# PCB_Ver_1_0.net
KiCad netlist of a schematic drawn in Altium Designer
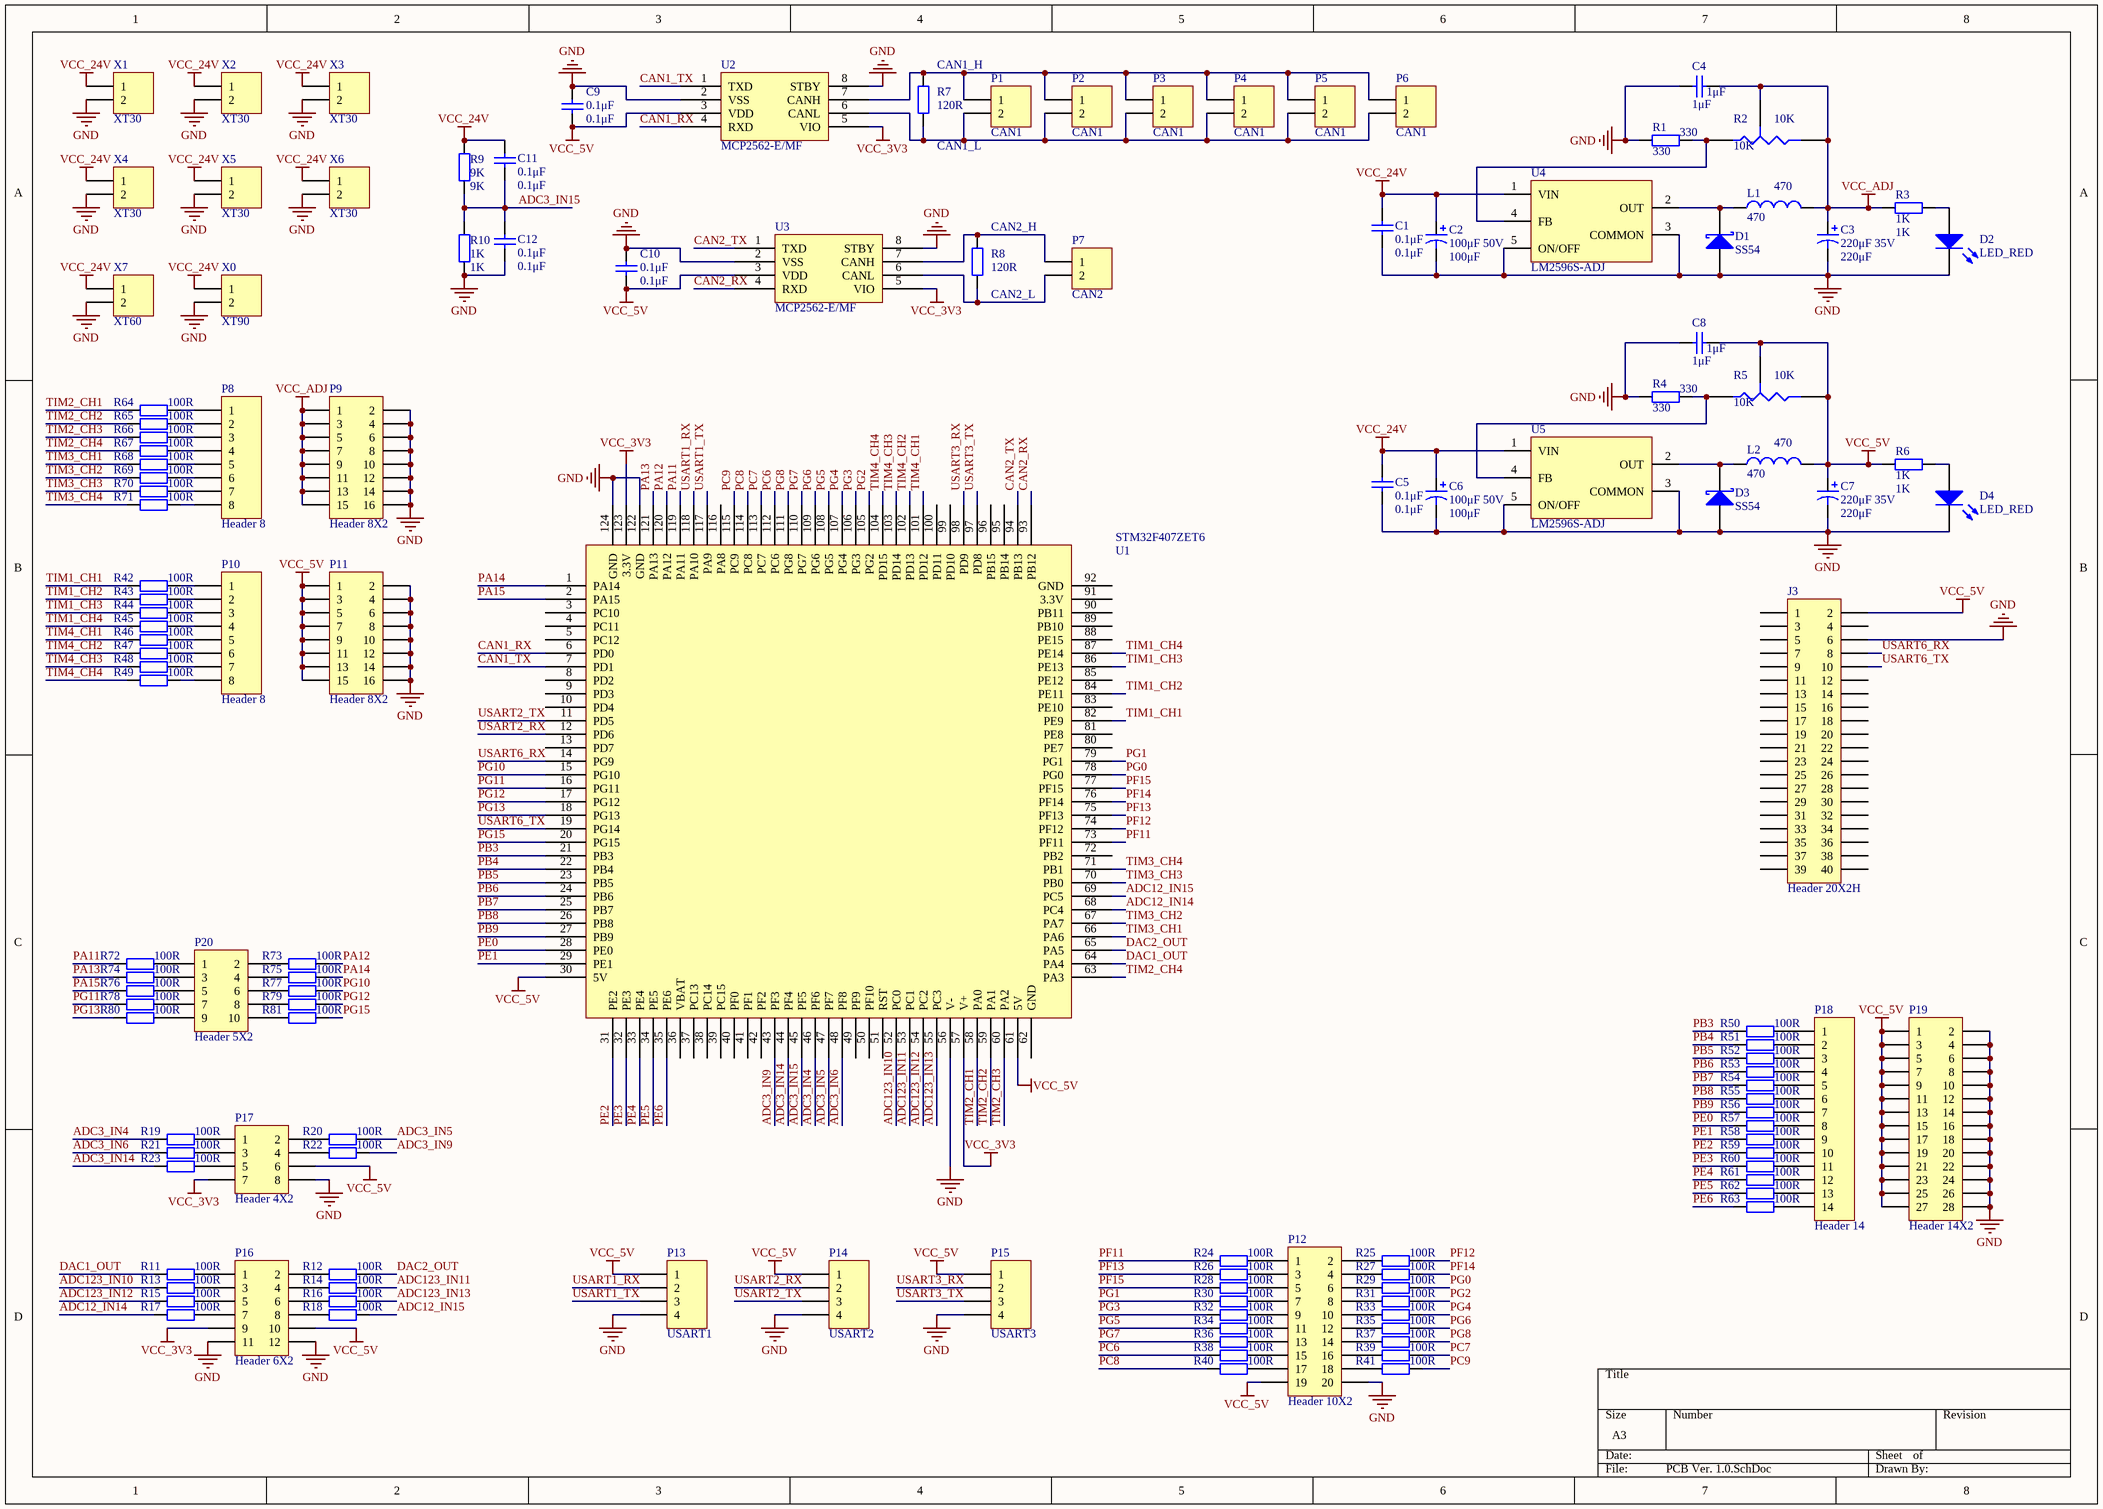
[diagram p0: PCB Ver. 1.0.SchDoc]

(export (version "E")
  (design (tool "Eeschema 10.0.6"))
  (components
    (comp (ref "C1")
      (value "0.1μF")
      (footprint "6-0805_N")
      (description "Capacitor")
      (fields (field (name "ALTIUM_VALUE") "0.1μF") (field (name "PUBLISHER") "Altium Limited"))
      (libsource (lib "Miscellaneous Devices") (part "Cap"))
    )
    (comp (ref "C2")
      (value "100μF 50V")
      (footprint "8*12直插铝电解")
      (description "Polarized Capacitor (Radial)")
      (fields (field (name "ALTIUM_VALUE") "100μF") (field (name "PUBLISHER") "Altium Limited"))
      (libsource (lib "Miscellaneous Devices") (part "Cap Pol1"))
    )
    (comp (ref "C3")
      (value "220μF 35V")
      (footprint "8*12直插铝电解")
      (description "Polarized Capacitor (Radial)")
      (fields (field (name "ALTIUM_VALUE") "220μF") (field (name "PUBLISHER") "Altium Limited"))
      (libsource (lib "Miscellaneous Devices") (part "Cap Pol1"))
    )
    (comp (ref "C4")
      (value "1μF")
      (footprint "6-0805_N")
      (description "Capacitor")
      (fields (field (name "ALTIUM_VALUE") "1μF") (field (name "PUBLISHER") "Altium Limited"))
      (libsource (lib "Miscellaneous Devices") (part "Cap"))
    )
    (comp (ref "C5")
      (value "0.1μF")
      (footprint "6-0805_N")
      (description "Capacitor")
      (fields (field (name "ALTIUM_VALUE") "0.1μF") (field (name "PUBLISHER") "Altium Limited"))
      (libsource (lib "Miscellaneous Devices") (part "Cap"))
    )
    (comp (ref "C6")
      (value "100μF 50V")
      (footprint "8*12直插铝电解")
      (description "Polarized Capacitor (Radial)")
      (fields (field (name "ALTIUM_VALUE") "100μF") (field (name "PUBLISHER") "Altium Limited"))
      (libsource (lib "Miscellaneous Devices") (part "Cap Pol1"))
    )
    (comp (ref "C7")
      (value "220μF 35V")
      (footprint "8*12直插铝电解")
      (description "Polarized Capacitor (Radial)")
      (fields (field (name "ALTIUM_VALUE") "220μF") (field (name "PUBLISHER") "Altium Limited"))
      (libsource (lib "Miscellaneous Devices") (part "Cap Pol1"))
    )
    (comp (ref "C8")
      (value "1μF")
      (footprint "6-0805_N")
      (description "Capacitor")
      (fields (field (name "ALTIUM_VALUE") "1μF") (field (name "PUBLISHER") "Altium Limited"))
      (libsource (lib "Miscellaneous Devices") (part "Cap"))
    )
    (comp (ref "C9")
      (value "0.1μF")
      (footprint "6-0805_N")
      (description "Capacitor")
      (fields (field (name "ALTIUM_VALUE") "0.1μF") (field (name "PUBLISHER") "Altium Limited"))
      (libsource (lib "Miscellaneous Devices") (part "Cap"))
    )
    (comp (ref "C10")
      (value "0.1μF")
      (footprint "6-0805_N")
      (description "Capacitor")
      (fields (field (name "ALTIUM_VALUE") "0.1μF") (field (name "PUBLISHER") "Altium Limited"))
      (libsource (lib "Miscellaneous Devices") (part "Cap"))
    )
    (comp (ref "C11")
      (value "0.1μF")
      (footprint "6-0805_N")
      (description "Capacitor")
      (fields (field (name "ALTIUM_VALUE") "0.1μF") (field (name "PUBLISHER") "Altium Limited"))
      (libsource (lib "Miscellaneous Devices") (part "Cap"))
    )
    (comp (ref "C12")
      (value "0.1μF")
      (footprint "6-0805_N")
      (description "Capacitor")
      (fields (field (name "ALTIUM_VALUE") "0.1μF") (field (name "PUBLISHER") "Altium Limited"))
      (libsource (lib "Miscellaneous Devices") (part "Cap"))
    )
    (comp (ref "D1")
      (value "SS54")
      (footprint "DO-214AA")
      (description "Schottky Rectifier")
      (fields (field (name "PUBLISHER") "Altium Limited"))
      (libsource (lib "Miscellaneous Devices") (part "Diode 11DQ03"))
    )
    (comp (ref "D2")
      (value "LED_RED")
      (footprint "1206_LED")
      (description "Typical BLUE SiC LED")
      (fields (field (name "PUBLISHER") "Altium Limited"))
      (libsource (lib "Miscellaneous Devices") (part "LED3"))
    )
    (comp (ref "D3")
      (value "SS54")
      (footprint "DO-214AA")
      (description "Schottky Rectifier")
      (fields (field (name "PUBLISHER") "Altium Limited"))
      (libsource (lib "Miscellaneous Devices") (part "Diode 11DQ03"))
    )
    (comp (ref "D4")
      (value "LED_RED")
      (footprint "1206_LED")
      (description "Typical BLUE SiC LED")
      (fields (field (name "PUBLISHER") "Altium Limited"))
      (libsource (lib "Miscellaneous Devices") (part "LED3"))
    )
    (comp (ref "J3")
      (value "Header 20X2H")
      (footprint "HDR2X20")
      (description "Header, 20-Pin, Dual row, Right Angle")
      (fields (field (name "PUBLISHER") "Altium Limited"))
      (libsource (lib "Miscellaneous Connectors") (part "Header 20X2H"))
    )
    (comp (ref "L1")
      (value "470")
      (footprint "12*12*7贴片电感")
      (description "Inductor")
      (fields (field (name "ALTIUM_VALUE") "470") (field (name "PUBLISHER") "Altium Limited"))
      (libsource (lib "Miscellaneous Devices") (part "Inductor"))
    )
    (comp (ref "L2")
      (value "470")
      (footprint "12*12*7贴片电感")
      (description "Inductor")
      (fields (field (name "ALTIUM_VALUE") "470") (field (name "PUBLISHER") "Altium Limited"))
      (libsource (lib "Miscellaneous Devices") (part "Inductor"))
    )
    (comp (ref "P1")
      (value "CAN1")
      (footprint "MHDR1X2")
      (description "Header, 2-Pin")
      (fields (field (name "PUBLISHER") "Altium Limited"))
      (libsource (lib "Miscellaneous Connectors") (part "Header 2"))
    )
    (comp (ref "P2")
      (value "CAN1")
      (footprint "MHDR1X2")
      (description "Header, 2-Pin")
      (fields (field (name "PUBLISHER") "Altium Limited"))
      (libsource (lib "Miscellaneous Connectors") (part "Header 2"))
    )
    (comp (ref "P3")
      (value "CAN1")
      (footprint "MHDR1X2")
      (description "Header, 2-Pin")
      (fields (field (name "PUBLISHER") "Altium Limited"))
      (libsource (lib "Miscellaneous Connectors") (part "Header 2"))
    )
    (comp (ref "P4")
      (value "CAN1")
      (footprint "MHDR1X2")
      (description "Header, 2-Pin")
      (fields (field (name "PUBLISHER") "Altium Limited"))
      (libsource (lib "Miscellaneous Connectors") (part "Header 2"))
    )
    (comp (ref "P5")
      (value "CAN1")
      (footprint "MHDR1X2")
      (description "Header, 2-Pin")
      (fields (field (name "PUBLISHER") "Altium Limited"))
      (libsource (lib "Miscellaneous Connectors") (part "Header 2"))
    )
    (comp (ref "P6")
      (value "CAN1")
      (footprint "MHDR1X2")
      (description "Header, 2-Pin")
      (fields (field (name "PUBLISHER") "Altium Limited"))
      (libsource (lib "Miscellaneous Connectors") (part "Header 2"))
    )
    (comp (ref "P7")
      (value "CAN2")
      (footprint "HDR1X2")
      (description "Header, 2-Pin")
      (fields (field (name "PUBLISHER") "Altium Limited"))
      (libsource (lib "Miscellaneous Connectors") (part "Header 2"))
    )
    (comp (ref "P8")
      (value "Header 8")
      (footprint "HDR1X8")
      (description "Header, 8-Pin")
      (fields (field (name "PUBLISHER") "Altium Limited"))
      (libsource (lib "Miscellaneous Connectors") (part "Header 8"))
    )
    (comp (ref "P9")
      (value "Header 8X2")
      (footprint "HDR2X8")
      (description "Header, 8-Pin, Dual row")
      (fields (field (name "PUBLISHER") "Altium Limited"))
      (libsource (lib "Miscellaneous Connectors") (part "Header 8X2"))
    )
    (comp (ref "P10")
      (value "Header 8")
      (footprint "HDR1X8")
      (description "Header, 8-Pin")
      (fields (field (name "PUBLISHER") "Altium Limited"))
      (libsource (lib "Miscellaneous Connectors") (part "Header 8"))
    )
    (comp (ref "P11")
      (value "Header 8X2")
      (footprint "HDR2X8")
      (description "Header, 8-Pin, Dual row")
      (fields (field (name "PUBLISHER") "Altium Limited"))
      (libsource (lib "Miscellaneous Connectors") (part "Header 8X2"))
    )
    (comp (ref "P12")
      (value "Header 10X2")
      (footprint "HDR2X10")
      (description "Header, 10-Pin, Dual row")
      (fields (field (name "PUBLISHER") "Altium Limited"))
      (libsource (lib "Miscellaneous Connectors") (part "Header 10X2"))
    )
    (comp (ref "P13")
      (value "USART1")
      (footprint "HDR1X4")
      (description "Header, 4-Pin")
      (fields (field (name "PUBLISHER") "Altium Limited"))
      (libsource (lib "Miscellaneous Connectors") (part "Header 4"))
    )
    (comp (ref "P14")
      (value "USART2")
      (footprint "HDR1X4")
      (description "Header, 4-Pin")
      (fields (field (name "PUBLISHER") "Altium Limited"))
      (libsource (lib "Miscellaneous Connectors") (part "Header 4"))
    )
    (comp (ref "P15")
      (value "USART3")
      (footprint "HDR1X4")
      (description "Header, 4-Pin")
      (fields (field (name "PUBLISHER") "Altium Limited"))
      (libsource (lib "Miscellaneous Connectors") (part "Header 4"))
    )
    (comp (ref "P16")
      (value "Header 6X2")
      (footprint "HDR2X6")
      (description "Header, 6-Pin, Dual row")
      (fields (field (name "PUBLISHER") "Altium Limited"))
      (libsource (lib "Miscellaneous Connectors") (part "Header 6X2"))
    )
    (comp (ref "P17")
      (value "Header 4X2")
      (footprint "HDR2X4")
      (description "Header, 4-Pin, Dual row")
      (fields (field (name "PUBLISHER") "Altium Limited"))
      (libsource (lib "Miscellaneous Connectors") (part "Header 4X2"))
    )
    (comp (ref "P18")
      (value "Header 14")
      (footprint "HDR1X14")
      (description "Header, 14-Pin")
      (fields (field (name "PUBLISHER") "Altium Limited"))
      (libsource (lib "Miscellaneous Connectors") (part "Header 14"))
    )
    (comp (ref "P19")
      (value "Header 14X2")
      (footprint "HDR2X14")
      (description "Header, 14-Pin, Dual row")
      (fields (field (name "PUBLISHER") "Altium Limited"))
      (libsource (lib "Miscellaneous Connectors") (part "Header 14X2"))
    )
    (comp (ref "P20")
      (value "Header 5X2")
      (footprint "HDR2X5")
      (description "Header, 5-Pin, Dual row")
      (fields (field (name "PUBLISHER") "Altium Limited"))
      (libsource (lib "Miscellaneous Connectors") (part "Header 5X2"))
    )
    (comp (ref "R1")
      (value "330")
      (footprint "6-0805_N")
      (description "Resistor")
      (fields (field (name "ALTIUM_VALUE") "330") (field (name "PUBLISHER") "Altium Limited"))
      (libsource (lib "Miscellaneous Devices") (part "Res2"))
    )
    (comp (ref "R2")
      (value "10K")
      (footprint "3296W精密电位器")
      (description "Tapped Resistor")
      (fields (field (name "ALTIUM_VALUE") "10K") (field (name "PUBLISHER") "Altium Limited"))
      (libsource (lib "Miscellaneous Devices") (part "Res Tap"))
    )
    (comp (ref "R3")
      (value "1K")
      (footprint "6-0805_N")
      (description "Resistor")
      (fields (field (name "ALTIUM_VALUE") "1K") (field (name "PUBLISHER") "Altium Limited"))
      (libsource (lib "Miscellaneous Devices") (part "Res2"))
    )
    (comp (ref "R4")
      (value "330")
      (footprint "6-0805_N")
      (description "Resistor")
      (fields (field (name "ALTIUM_VALUE") "330") (field (name "PUBLISHER") "Altium Limited"))
      (libsource (lib "Miscellaneous Devices") (part "Res2"))
    )
    (comp (ref "R5")
      (value "10K")
      (footprint "3296W精密电位器")
      (description "Tapped Resistor")
      (fields (field (name "ALTIUM_VALUE") "10K") (field (name "PUBLISHER") "Altium Limited"))
      (libsource (lib "Miscellaneous Devices") (part "Res Tap"))
    )
    (comp (ref "R6")
      (value "1K")
      (footprint "6-0805_N")
      (description "Resistor")
      (fields (field (name "ALTIUM_VALUE") "1K") (field (name "PUBLISHER") "Altium Limited"))
      (libsource (lib "Miscellaneous Devices") (part "Res2"))
    )
    (comp (ref "R7")
      (value "120R")
      (footprint "6-0805_N")
      (description "Resistor")
      (fields (field (name "PUBLISHER") "Altium Limited"))
      (libsource (lib "") (part "Res2_1"))
    )
    (comp (ref "R8")
      (value "120R")
      (footprint "6-0805_N")
      (description "Resistor")
      (fields (field (name "PUBLISHER") "Altium Limited"))
      (libsource (lib "") (part "Res2_1"))
    )
    (comp (ref "R9")
      (value "9K")
      (footprint "6-0805_N")
      (description "Resistor")
      (fields (field (name "ALTIUM_VALUE") "9K") (field (name "PUBLISHER") "Altium Limited"))
      (libsource (lib "") (part "Res2_1"))
    )
    (comp (ref "R10")
      (value "1K")
      (footprint "6-0805_N")
      (description "Resistor")
      (fields (field (name "ALTIUM_VALUE") "1K") (field (name "PUBLISHER") "Altium Limited"))
      (libsource (lib "") (part "Res2_1"))
    )
    (comp (ref "R11")
      (value "100R")
      (footprint "6-0805_N")
      (description "Resistor")
      (fields (field (name "PUBLISHER") "Altium Limited"))
      (libsource (lib "Miscellaneous Devices") (part "Res2"))
    )
    (comp (ref "R12")
      (value "100R")
      (footprint "6-0805_N")
      (description "Resistor")
      (fields (field (name "PUBLISHER") "Altium Limited"))
      (libsource (lib "Miscellaneous Devices") (part "Res2"))
    )
    (comp (ref "R13")
      (value "100R")
      (footprint "6-0805_N")
      (description "Resistor")
      (fields (field (name "PUBLISHER") "Altium Limited"))
      (libsource (lib "Miscellaneous Devices") (part "Res2"))
    )
    (comp (ref "R14")
      (value "100R")
      (footprint "6-0805_N")
      (description "Resistor")
      (fields (field (name "PUBLISHER") "Altium Limited"))
      (libsource (lib "Miscellaneous Devices") (part "Res2"))
    )
    (comp (ref "R15")
      (value "100R")
      (footprint "6-0805_N")
      (description "Resistor")
      (fields (field (name "PUBLISHER") "Altium Limited"))
      (libsource (lib "Miscellaneous Devices") (part "Res2"))
    )
    (comp (ref "R16")
      (value "100R")
      (footprint "6-0805_N")
      (description "Resistor")
      (fields (field (name "PUBLISHER") "Altium Limited"))
      (libsource (lib "Miscellaneous Devices") (part "Res2"))
    )
    (comp (ref "R17")
      (value "100R")
      (footprint "6-0805_N")
      (description "Resistor")
      (fields (field (name "PUBLISHER") "Altium Limited"))
      (libsource (lib "Miscellaneous Devices") (part "Res2"))
    )
    (comp (ref "R18")
      (value "100R")
      (footprint "6-0805_N")
      (description "Resistor")
      (fields (field (name "PUBLISHER") "Altium Limited"))
      (libsource (lib "Miscellaneous Devices") (part "Res2"))
    )
    (comp (ref "R19")
      (value "100R")
      (footprint "6-0805_N")
      (description "Resistor")
      (fields (field (name "PUBLISHER") "Altium Limited"))
      (libsource (lib "Miscellaneous Devices") (part "Res2"))
    )
    (comp (ref "R20")
      (value "100R")
      (footprint "6-0805_N")
      (description "Resistor")
      (fields (field (name "PUBLISHER") "Altium Limited"))
      (libsource (lib "Miscellaneous Devices") (part "Res2"))
    )
    (comp (ref "R21")
      (value "100R")
      (footprint "6-0805_N")
      (description "Resistor")
      (fields (field (name "PUBLISHER") "Altium Limited"))
      (libsource (lib "Miscellaneous Devices") (part "Res2"))
    )
    (comp (ref "R22")
      (value "100R")
      (footprint "6-0805_N")
      (description "Resistor")
      (fields (field (name "PUBLISHER") "Altium Limited"))
      (libsource (lib "Miscellaneous Devices") (part "Res2"))
    )
    (comp (ref "R23")
      (value "100R")
      (footprint "6-0805_N")
      (description "Resistor")
      (fields (field (name "PUBLISHER") "Altium Limited"))
      (libsource (lib "Miscellaneous Devices") (part "Res2"))
    )
    (comp (ref "R24")
      (value "100R")
      (footprint "6-0805_N")
      (description "Resistor")
      (fields (field (name "PUBLISHER") "Altium Limited"))
      (libsource (lib "Miscellaneous Devices") (part "Res2"))
    )
    (comp (ref "R25")
      (value "100R")
      (footprint "6-0805_N")
      (description "Resistor")
      (fields (field (name "PUBLISHER") "Altium Limited"))
      (libsource (lib "Miscellaneous Devices") (part "Res2"))
    )
    (comp (ref "R26")
      (value "100R")
      (footprint "6-0805_N")
      (description "Resistor")
      (fields (field (name "PUBLISHER") "Altium Limited"))
      (libsource (lib "Miscellaneous Devices") (part "Res2"))
    )
    (comp (ref "R27")
      (value "100R")
      (footprint "6-0805_N")
      (description "Resistor")
      (fields (field (name "PUBLISHER") "Altium Limited"))
      (libsource (lib "Miscellaneous Devices") (part "Res2"))
    )
    (comp (ref "R28")
      (value "100R")
      (footprint "6-0805_N")
      (description "Resistor")
      (fields (field (name "PUBLISHER") "Altium Limited"))
      (libsource (lib "Miscellaneous Devices") (part "Res2"))
    )
    (comp (ref "R29")
      (value "100R")
      (footprint "6-0805_N")
      (description "Resistor")
      (fields (field (name "PUBLISHER") "Altium Limited"))
      (libsource (lib "Miscellaneous Devices") (part "Res2"))
    )
    (comp (ref "R30")
      (value "100R")
      (footprint "6-0805_N")
      (description "Resistor")
      (fields (field (name "PUBLISHER") "Altium Limited"))
      (libsource (lib "Miscellaneous Devices") (part "Res2"))
    )
    (comp (ref "R31")
      (value "100R")
      (footprint "6-0805_N")
      (description "Resistor")
      (fields (field (name "PUBLISHER") "Altium Limited"))
      (libsource (lib "Miscellaneous Devices") (part "Res2"))
    )
    (comp (ref "R32")
      (value "100R")
      (footprint "6-0805_N")
      (description "Resistor")
      (fields (field (name "PUBLISHER") "Altium Limited"))
      (libsource (lib "Miscellaneous Devices") (part "Res2"))
    )
    (comp (ref "R33")
      (value "100R")
      (footprint "6-0805_N")
      (description "Resistor")
      (fields (field (name "PUBLISHER") "Altium Limited"))
      (libsource (lib "Miscellaneous Devices") (part "Res2"))
    )
    (comp (ref "R34")
      (value "100R")
      (footprint "6-0805_N")
      (description "Resistor")
      (fields (field (name "PUBLISHER") "Altium Limited"))
      (libsource (lib "Miscellaneous Devices") (part "Res2"))
    )
    (comp (ref "R35")
      (value "100R")
      (footprint "6-0805_N")
      (description "Resistor")
      (fields (field (name "PUBLISHER") "Altium Limited"))
      (libsource (lib "Miscellaneous Devices") (part "Res2"))
    )
    (comp (ref "R36")
      (value "100R")
      (footprint "6-0805_N")
      (description "Resistor")
      (fields (field (name "PUBLISHER") "Altium Limited"))
      (libsource (lib "Miscellaneous Devices") (part "Res2"))
    )
    (comp (ref "R37")
      (value "100R")
      (footprint "6-0805_N")
      (description "Resistor")
      (fields (field (name "PUBLISHER") "Altium Limited"))
      (libsource (lib "Miscellaneous Devices") (part "Res2"))
    )
    (comp (ref "R38")
      (value "100R")
      (footprint "6-0805_N")
      (description "Resistor")
      (fields (field (name "PUBLISHER") "Altium Limited"))
      (libsource (lib "Miscellaneous Devices") (part "Res2"))
    )
    (comp (ref "R39")
      (value "100R")
      (footprint "6-0805_N")
      (description "Resistor")
      (fields (field (name "PUBLISHER") "Altium Limited"))
      (libsource (lib "Miscellaneous Devices") (part "Res2"))
    )
    (comp (ref "R40")
      (value "100R")
      (footprint "6-0805_N")
      (description "Resistor")
      (fields (field (name "PUBLISHER") "Altium Limited"))
      (libsource (lib "Miscellaneous Devices") (part "Res2"))
    )
    (comp (ref "R41")
      (value "100R")
      (footprint "6-0805_N")
      (description "Resistor")
      (fields (field (name "PUBLISHER") "Altium Limited"))
      (libsource (lib "Miscellaneous Devices") (part "Res2"))
    )
    (comp (ref "R42")
      (value "100R")
      (footprint "6-0805_N")
      (description "Resistor")
      (fields (field (name "PUBLISHER") "Altium Limited"))
      (libsource (lib "Miscellaneous Devices") (part "Res2"))
    )
    (comp (ref "R43")
      (value "100R")
      (footprint "6-0805_N")
      (description "Resistor")
      (fields (field (name "PUBLISHER") "Altium Limited"))
      (libsource (lib "Miscellaneous Devices") (part "Res2"))
    )
    (comp (ref "R44")
      (value "100R")
      (footprint "6-0805_N")
      (description "Resistor")
      (fields (field (name "PUBLISHER") "Altium Limited"))
      (libsource (lib "Miscellaneous Devices") (part "Res2"))
    )
    (comp (ref "R45")
      (value "100R")
      (footprint "6-0805_N")
      (description "Resistor")
      (fields (field (name "PUBLISHER") "Altium Limited"))
      (libsource (lib "Miscellaneous Devices") (part "Res2"))
    )
    (comp (ref "R46")
      (value "100R")
      (footprint "6-0805_N")
      (description "Resistor")
      (fields (field (name "PUBLISHER") "Altium Limited"))
      (libsource (lib "Miscellaneous Devices") (part "Res2"))
    )
    (comp (ref "R47")
      (value "100R")
      (footprint "6-0805_N")
      (description "Resistor")
      (fields (field (name "PUBLISHER") "Altium Limited"))
      (libsource (lib "Miscellaneous Devices") (part "Res2"))
    )
    (comp (ref "R48")
      (value "100R")
      (footprint "6-0805_N")
      (description "Resistor")
      (fields (field (name "PUBLISHER") "Altium Limited"))
      (libsource (lib "Miscellaneous Devices") (part "Res2"))
    )
    (comp (ref "R49")
      (value "100R")
      (footprint "6-0805_N")
      (description "Resistor")
      (fields (field (name "PUBLISHER") "Altium Limited"))
      (libsource (lib "Miscellaneous Devices") (part "Res2"))
    )
    (comp (ref "R50")
      (value "100R")
      (footprint "6-0805_N")
      (description "Resistor")
      (fields (field (name "PUBLISHER") "Altium Limited"))
      (libsource (lib "Miscellaneous Devices") (part "Res2"))
    )
    (comp (ref "R51")
      (value "100R")
      (footprint "6-0805_N")
      (description "Resistor")
      (fields (field (name "PUBLISHER") "Altium Limited"))
      (libsource (lib "Miscellaneous Devices") (part "Res2"))
    )
    (comp (ref "R52")
      (value "100R")
      (footprint "6-0805_N")
      (description "Resistor")
      (fields (field (name "PUBLISHER") "Altium Limited"))
      (libsource (lib "Miscellaneous Devices") (part "Res2"))
    )
    (comp (ref "R53")
      (value "100R")
      (footprint "6-0805_N")
      (description "Resistor")
      (fields (field (name "PUBLISHER") "Altium Limited"))
      (libsource (lib "Miscellaneous Devices") (part "Res2"))
    )
    (comp (ref "R54")
      (value "100R")
      (footprint "6-0805_N")
      (description "Resistor")
      (fields (field (name "PUBLISHER") "Altium Limited"))
      (libsource (lib "Miscellaneous Devices") (part "Res2"))
    )
    (comp (ref "R55")
      (value "100R")
      (footprint "6-0805_N")
      (description "Resistor")
      (fields (field (name "PUBLISHER") "Altium Limited"))
      (libsource (lib "Miscellaneous Devices") (part "Res2"))
    )
    (comp (ref "R56")
      (value "100R")
      (footprint "6-0805_N")
      (description "Resistor")
      (fields (field (name "PUBLISHER") "Altium Limited"))
      (libsource (lib "Miscellaneous Devices") (part "Res2"))
    )
    (comp (ref "R57")
      (value "100R")
      (footprint "6-0805_N")
      (description "Resistor")
      (fields (field (name "PUBLISHER") "Altium Limited"))
      (libsource (lib "Miscellaneous Devices") (part "Res2"))
    )
    (comp (ref "R58")
      (value "100R")
      (footprint "6-0805_N")
      (description "Resistor")
      (fields (field (name "PUBLISHER") "Altium Limited"))
      (libsource (lib "Miscellaneous Devices") (part "Res2"))
    )
    (comp (ref "R59")
      (value "100R")
      (footprint "6-0805_N")
      (description "Resistor")
      (fields (field (name "PUBLISHER") "Altium Limited"))
      (libsource (lib "Miscellaneous Devices") (part "Res2"))
    )
    (comp (ref "R60")
      (value "100R")
      (footprint "6-0805_N")
      (description "Resistor")
      (fields (field (name "PUBLISHER") "Altium Limited"))
      (libsource (lib "Miscellaneous Devices") (part "Res2"))
    )
    (comp (ref "R61")
      (value "100R")
      (footprint "6-0805_N")
      (description "Resistor")
      (fields (field (name "PUBLISHER") "Altium Limited"))
      (libsource (lib "Miscellaneous Devices") (part "Res2"))
    )
    (comp (ref "R62")
      (value "100R")
      (footprint "6-0805_N")
      (description "Resistor")
      (fields (field (name "PUBLISHER") "Altium Limited"))
      (libsource (lib "Miscellaneous Devices") (part "Res2"))
    )
    (comp (ref "R63")
      (value "100R")
      (footprint "6-0805_N")
      (description "Resistor")
      (fields (field (name "PUBLISHER") "Altium Limited"))
      (libsource (lib "Miscellaneous Devices") (part "Res2"))
    )
    (comp (ref "R64")
      (value "100R")
      (footprint "6-0805_N")
      (description "Resistor")
      (fields (field (name "PUBLISHER") "Altium Limited"))
      (libsource (lib "Miscellaneous Devices") (part "Res2"))
    )
    (comp (ref "R65")
      (value "100R")
      (footprint "6-0805_N")
      (description "Resistor")
      (fields (field (name "PUBLISHER") "Altium Limited"))
      (libsource (lib "Miscellaneous Devices") (part "Res2"))
    )
    (comp (ref "R66")
      (value "100R")
      (footprint "6-0805_N")
      (description "Resistor")
      (fields (field (name "PUBLISHER") "Altium Limited"))
      (libsource (lib "Miscellaneous Devices") (part "Res2"))
    )
    (comp (ref "R67")
      (value "100R")
      (footprint "6-0805_N")
      (description "Resistor")
      (fields (field (name "PUBLISHER") "Altium Limited"))
      (libsource (lib "Miscellaneous Devices") (part "Res2"))
    )
    (comp (ref "R68")
      (value "100R")
      (footprint "6-0805_N")
      (description "Resistor")
      (fields (field (name "PUBLISHER") "Altium Limited"))
      (libsource (lib "Miscellaneous Devices") (part "Res2"))
    )
    (comp (ref "R69")
      (value "100R")
      (footprint "6-0805_N")
      (description "Resistor")
      (fields (field (name "PUBLISHER") "Altium Limited"))
      (libsource (lib "Miscellaneous Devices") (part "Res2"))
    )
    (comp (ref "R70")
      (value "100R")
      (footprint "6-0805_N")
      (description "Resistor")
      (fields (field (name "PUBLISHER") "Altium Limited"))
      (libsource (lib "Miscellaneous Devices") (part "Res2"))
    )
    (comp (ref "R71")
      (value "100R")
      (footprint "6-0805_N")
      (description "Resistor")
      (fields (field (name "PUBLISHER") "Altium Limited"))
      (libsource (lib "Miscellaneous Devices") (part "Res2"))
    )
    (comp (ref "R72")
      (value "100R")
      (footprint "6-0805_N")
      (description "Resistor")
      (fields (field (name "PUBLISHER") "Altium Limited"))
      (libsource (lib "Miscellaneous Devices") (part "Res2"))
    )
    (comp (ref "R73")
      (value "100R")
      (footprint "6-0805_N")
      (description "Resistor")
      (fields (field (name "PUBLISHER") "Altium Limited"))
      (libsource (lib "Miscellaneous Devices") (part "Res2"))
    )
    (comp (ref "R74")
      (value "100R")
      (footprint "6-0805_N")
      (description "Resistor")
      (fields (field (name "PUBLISHER") "Altium Limited"))
      (libsource (lib "Miscellaneous Devices") (part "Res2"))
    )
    (comp (ref "R75")
      (value "100R")
      (footprint "6-0805_N")
      (description "Resistor")
      (fields (field (name "PUBLISHER") "Altium Limited"))
      (libsource (lib "Miscellaneous Devices") (part "Res2"))
    )
    (comp (ref "R76")
      (value "100R")
      (footprint "6-0805_N")
      (description "Resistor")
      (fields (field (name "PUBLISHER") "Altium Limited"))
      (libsource (lib "Miscellaneous Devices") (part "Res2"))
    )
    (comp (ref "R77")
      (value "100R")
      (footprint "6-0805_N")
      (description "Resistor")
      (fields (field (name "PUBLISHER") "Altium Limited"))
      (libsource (lib "Miscellaneous Devices") (part "Res2"))
    )
    (comp (ref "R78")
      (value "100R")
      (footprint "6-0805_N")
      (description "Resistor")
      (fields (field (name "PUBLISHER") "Altium Limited"))
      (libsource (lib "Miscellaneous Devices") (part "Res2"))
    )
    (comp (ref "R79")
      (value "100R")
      (footprint "6-0805_N")
      (description "Resistor")
      (fields (field (name "PUBLISHER") "Altium Limited"))
      (libsource (lib "Miscellaneous Devices") (part "Res2"))
    )
    (comp (ref "R80")
      (value "100R")
      (footprint "6-0805_N")
      (description "Resistor")
      (fields (field (name "PUBLISHER") "Altium Limited"))
      (libsource (lib "Miscellaneous Devices") (part "Res2"))
    )
    (comp (ref "R81")
      (value "100R")
      (footprint "6-0805_N")
      (description "Resistor")
      (fields (field (name "PUBLISHER") "Altium Limited"))
      (libsource (lib "Miscellaneous Devices") (part "Res2"))
    )
    (comp (ref "STM32F407ZET6")
      (value "U1")
      (footprint "STM32F103ZET6")
      (libsource (lib "STM32F407ZET6") (part "Component_1"))
    )
    (comp (ref "U2")
      (value "MCP2562-E/MF")
      (footprint "SO-8")
      (libsource (lib "TempLibraries") (part "MCP2562-E/MF"))
    )
    (comp (ref "U3")
      (value "MCP2562-E/MF")
      (footprint "SO-8")
      (libsource (lib "TempLibraries") (part "MCP2562-E/MF"))
    )
    (comp (ref "U4")
      (value "LM2596S-ADJ")
      (footprint "TO-263")
      (description "CI-LM2576S-5.0")
      (libsource (lib "IC") (part "LM2576S-5.0"))
    )
    (comp (ref "U5")
      (value "LM2596S-ADJ")
      (footprint "TO-263")
      (description "CI-LM2576S-5.0")
      (libsource (lib "IC") (part "LM2576S-5.0"))
    )
    (comp (ref "X0")
      (value "XT90")
      (footprint "XT90PB")
      (description "Header, 2-Pin")
      (fields (field (name "PUBLISHER") "Altium Limited"))
      (libsource (lib "Miscellaneous Connectors") (part "Header 2"))
    )
    (comp (ref "X1")
      (value "XT30")
      (footprint "XT30UPB")
      (description "Header, 2-Pin")
      (fields (field (name "PUBLISHER") "Altium Limited"))
      (libsource (lib "Miscellaneous Connectors") (part "Header 2"))
    )
    (comp (ref "X2")
      (value "XT30")
      (footprint "XT30UPB")
      (description "Header, 2-Pin")
      (fields (field (name "PUBLISHER") "Altium Limited"))
      (libsource (lib "Miscellaneous Connectors") (part "Header 2"))
    )
    (comp (ref "X3")
      (value "XT30")
      (footprint "XT30UPB")
      (description "Header, 2-Pin")
      (fields (field (name "PUBLISHER") "Altium Limited"))
      (libsource (lib "Miscellaneous Connectors") (part "Header 2"))
    )
    (comp (ref "X4")
      (value "XT30")
      (footprint "XT30UPB")
      (description "Header, 2-Pin")
      (fields (field (name "PUBLISHER") "Altium Limited"))
      (libsource (lib "Miscellaneous Connectors") (part "Header 2"))
    )
    (comp (ref "X5")
      (value "XT30")
      (footprint "XT30UPB")
      (description "Header, 2-Pin")
      (fields (field (name "PUBLISHER") "Altium Limited"))
      (libsource (lib "Miscellaneous Connectors") (part "Header 2"))
    )
    (comp (ref "X6")
      (value "XT30")
      (footprint "XT30UPB")
      (description "Header, 2-Pin")
      (fields (field (name "PUBLISHER") "Altium Limited"))
      (libsource (lib "Miscellaneous Connectors") (part "Header 2"))
    )
    (comp (ref "X7")
      (value "XT60")
      (footprint "XT60PB")
      (description "Header, 2-Pin")
      (fields (field (name "PUBLISHER") "Altium Limited"))
      (libsource (lib "Miscellaneous Connectors") (part "Header 2"))
    )
  )
  (nets
    (net (code "1") (name "/ADC3_IN4") (class "Default")
      (node (ref "R19") (pin "1") (pinfunction "1_1") (pintype "passive"))
      (node (ref "STM32F407ZET6") (pin "46") (pinfunction "PF6_46") (pintype "passive"))
    )
    (net (code "2") (name "/ADC3_IN5") (class "Default")
      (node (ref "R20") (pin "2") (pinfunction "2_2") (pintype "passive"))
      (node (ref "STM32F407ZET6") (pin "47") (pinfunction "PF7_47") (pintype "passive"))
    )
    (net (code "3") (name "/ADC3_IN6") (class "Default")
      (node (ref "R21") (pin "1") (pinfunction "1_1") (pintype "passive"))
      (node (ref "STM32F407ZET6") (pin "48") (pinfunction "PF8_48") (pintype "passive"))
    )
    (net (code "4") (name "/ADC3_IN9") (class "Default")
      (node (ref "R22") (pin "2") (pinfunction "2_2") (pintype "passive"))
      (node (ref "STM32F407ZET6") (pin "43") (pinfunction "PF3_43") (pintype "passive"))
    )
    (net (code "5") (name "/ADC3_IN14") (class "Default")
      (node (ref "R23") (pin "1") (pinfunction "1_1") (pintype "passive"))
      (node (ref "STM32F407ZET6") (pin "44") (pinfunction "PF4_44") (pintype "passive"))
    )
    (net (code "6") (name "/ADC3_IN15") (class "Default")
      (node (ref "C11") (pin "1") (pinfunction "1_1") (pintype "passive"))
      (node (ref "C12") (pin "2") (pinfunction "2_2") (pintype "passive"))
      (node (ref "R10") (pin "2") (pinfunction "2_2") (pintype "passive"))
      (node (ref "R9") (pin "1") (pinfunction "1_1") (pintype "passive"))
      (node (ref "STM32F407ZET6") (pin "45") (pinfunction "PF5_45") (pintype "passive"))
    )
    (net (code "7") (name "/ADC12_IN14") (class "Default")
      (node (ref "R17") (pin "1") (pinfunction "1_1") (pintype "passive"))
      (node (ref "STM32F407ZET6") (pin "68") (pinfunction "PC4_68") (pintype "passive"))
    )
    (net (code "8") (name "/ADC12_IN15") (class "Default")
      (node (ref "R18") (pin "2") (pinfunction "2_2") (pintype "passive"))
      (node (ref "STM32F407ZET6") (pin "69") (pinfunction "PC5_69") (pintype "passive"))
    )
    (net (code "9") (name "/ADC123_IN10") (class "Default")
      (node (ref "R13") (pin "1") (pinfunction "1_1") (pintype "passive"))
      (node (ref "STM32F407ZET6") (pin "52") (pinfunction "PC0_52") (pintype "passive"))
    )
    (net (code "10") (name "/ADC123_IN11") (class "Default")
      (node (ref "R14") (pin "2") (pinfunction "2_2") (pintype "passive"))
      (node (ref "STM32F407ZET6") (pin "53") (pinfunction "PC1_53") (pintype "passive"))
    )
    (net (code "11") (name "/ADC123_IN12") (class "Default")
      (node (ref "R15") (pin "1") (pinfunction "1_1") (pintype "passive"))
      (node (ref "STM32F407ZET6") (pin "54") (pinfunction "PC2_54") (pintype "passive"))
    )
    (net (code "12") (name "/ADC123_IN13") (class "Default")
      (node (ref "R16") (pin "2") (pinfunction "2_2") (pintype "passive"))
      (node (ref "STM32F407ZET6") (pin "55") (pinfunction "PC3_55") (pintype "passive"))
    )
    (net (code "13") (name "/CAN1_RX") (class "Default")
      (node (ref "STM32F407ZET6") (pin "6") (pinfunction "PD0_6") (pintype "passive"))
      (node (ref "U2") (pin "4") (pinfunction "RXD_4") (pintype "passive"))
    )
    (net (code "14") (name "/CAN1_TX") (class "Default")
      (node (ref "STM32F407ZET6") (pin "7") (pinfunction "PD1_7") (pintype "passive"))
      (node (ref "U2") (pin "1") (pinfunction "TXD_1") (pintype "passive"))
    )
    (net (code "15") (name "/CAN2_RX") (class "Default")
      (node (ref "STM32F407ZET6") (pin "93") (pinfunction "PB12_93") (pintype "passive"))
      (node (ref "U3") (pin "4") (pinfunction "RXD_4") (pintype "passive"))
    )
    (net (code "16") (name "/CAN2_TX") (class "Default")
      (node (ref "STM32F407ZET6") (pin "94") (pinfunction "PB13_94") (pintype "passive"))
      (node (ref "U3") (pin "1") (pinfunction "TXD_1") (pintype "passive"))
    )
    (net (code "17") (name "/DAC1_OUT") (class "Default")
      (node (ref "R11") (pin "1") (pinfunction "1_1") (pintype "passive"))
      (node (ref "STM32F407ZET6") (pin "64") (pinfunction "PA4_64") (pintype "passive"))
    )
    (net (code "18") (name "/DAC2_OUT") (class "Default")
      (node (ref "R12") (pin "2") (pinfunction "2_2") (pintype "passive"))
      (node (ref "STM32F407ZET6") (pin "65") (pinfunction "PA5_65") (pintype "passive"))
    )
    (net (code "19") (name "/PA11") (class "Default")
      (node (ref "R72") (pin "1") (pinfunction "1_1") (pintype "passive"))
      (node (ref "STM32F407ZET6") (pin "119") (pinfunction "PA11_119") (pintype "passive"))
    )
    (net (code "20") (name "/PA12") (class "Default")
      (node (ref "R73") (pin "2") (pinfunction "2_2") (pintype "passive"))
      (node (ref "STM32F407ZET6") (pin "120") (pinfunction "PA12_120") (pintype "passive"))
    )
    (net (code "21") (name "/PA13") (class "Default")
      (node (ref "R74") (pin "1") (pinfunction "1_1") (pintype "passive"))
      (node (ref "STM32F407ZET6") (pin "121") (pinfunction "PA13_121") (pintype "passive"))
    )
    (net (code "22") (name "/PA14") (class "Default")
      (node (ref "R75") (pin "2") (pinfunction "2_2") (pintype "passive"))
      (node (ref "STM32F407ZET6") (pin "1") (pinfunction "PA14_1") (pintype "passive"))
    )
    (net (code "23") (name "/PA15") (class "Default")
      (node (ref "R76") (pin "1") (pinfunction "1_1") (pintype "passive"))
      (node (ref "STM32F407ZET6") (pin "2") (pinfunction "PA15_2") (pintype "passive"))
    )
    (net (code "24") (name "/PB3") (class "Default")
      (node (ref "R50") (pin "1") (pinfunction "1_1") (pintype "passive"))
      (node (ref "STM32F407ZET6") (pin "21") (pinfunction "PB3_21") (pintype "passive"))
    )
    (net (code "25") (name "/PB4") (class "Default")
      (node (ref "R51") (pin "1") (pinfunction "1_1") (pintype "passive"))
      (node (ref "STM32F407ZET6") (pin "22") (pinfunction "PB4_22") (pintype "passive"))
    )
    (net (code "26") (name "/PB5") (class "Default")
      (node (ref "R52") (pin "1") (pinfunction "1_1") (pintype "passive"))
      (node (ref "STM32F407ZET6") (pin "23") (pinfunction "PB5_23") (pintype "passive"))
    )
    (net (code "27") (name "/PB6") (class "Default")
      (node (ref "R53") (pin "1") (pinfunction "1_1") (pintype "passive"))
      (node (ref "STM32F407ZET6") (pin "24") (pinfunction "PB6_24") (pintype "passive"))
    )
    (net (code "28") (name "/PB7") (class "Default")
      (node (ref "R54") (pin "1") (pinfunction "1_1") (pintype "passive"))
      (node (ref "STM32F407ZET6") (pin "25") (pinfunction "PB7_25") (pintype "passive"))
    )
    (net (code "29") (name "/PB8") (class "Default")
      (node (ref "R55") (pin "1") (pinfunction "1_1") (pintype "passive"))
      (node (ref "STM32F407ZET6") (pin "26") (pinfunction "PB8_26") (pintype "passive"))
    )
    (net (code "30") (name "/PB9") (class "Default")
      (node (ref "R56") (pin "1") (pinfunction "1_1") (pintype "passive"))
      (node (ref "STM32F407ZET6") (pin "27") (pinfunction "PB9_27") (pintype "passive"))
    )
    (net (code "31") (name "/PC6") (class "Default")
      (node (ref "R38") (pin "1") (pinfunction "1_1") (pintype "passive"))
      (node (ref "STM32F407ZET6") (pin "112") (pinfunction "PC6_112") (pintype "passive"))
    )
    (net (code "32") (name "/PC7") (class "Default")
      (node (ref "R39") (pin "2") (pinfunction "2_2") (pintype "passive"))
      (node (ref "STM32F407ZET6") (pin "113") (pinfunction "PC7_113") (pintype "passive"))
    )
    (net (code "33") (name "/PC8") (class "Default")
      (node (ref "R40") (pin "1") (pinfunction "1_1") (pintype "passive"))
      (node (ref "STM32F407ZET6") (pin "114") (pinfunction "PC8_114") (pintype "passive"))
    )
    (net (code "34") (name "/PC9") (class "Default")
      (node (ref "R41") (pin "2") (pinfunction "2_2") (pintype "passive"))
      (node (ref "STM32F407ZET6") (pin "115") (pinfunction "PC9_115") (pintype "passive"))
    )
    (net (code "35") (name "/PE0") (class "Default")
      (node (ref "R57") (pin "1") (pinfunction "1_1") (pintype "passive"))
      (node (ref "STM32F407ZET6") (pin "28") (pinfunction "PE0_28") (pintype "passive"))
    )
    (net (code "36") (name "/PE1") (class "Default")
      (node (ref "R58") (pin "1") (pinfunction "1_1") (pintype "passive"))
      (node (ref "STM32F407ZET6") (pin "29") (pinfunction "PE1_29") (pintype "passive"))
    )
    (net (code "37") (name "/PE2") (class "Default")
      (node (ref "R59") (pin "1") (pinfunction "1_1") (pintype "passive"))
      (node (ref "STM32F407ZET6") (pin "31") (pinfunction "PE2_31") (pintype "passive"))
    )
    (net (code "38") (name "/PE3") (class "Default")
      (node (ref "R60") (pin "1") (pinfunction "1_1") (pintype "passive"))
      (node (ref "STM32F407ZET6") (pin "32") (pinfunction "PE3_32") (pintype "passive"))
    )
    (net (code "39") (name "/PE4") (class "Default")
      (node (ref "R61") (pin "1") (pinfunction "1_1") (pintype "passive"))
      (node (ref "STM32F407ZET6") (pin "33") (pinfunction "PE4_33") (pintype "passive"))
    )
    (net (code "40") (name "/PE5") (class "Default")
      (node (ref "R62") (pin "1") (pinfunction "1_1") (pintype "passive"))
      (node (ref "STM32F407ZET6") (pin "34") (pinfunction "PE5_34") (pintype "passive"))
    )
    (net (code "41") (name "/PE6") (class "Default")
      (node (ref "R63") (pin "1") (pinfunction "1_1") (pintype "passive"))
      (node (ref "STM32F407ZET6") (pin "35") (pinfunction "PE6_35") (pintype "passive"))
    )
    (net (code "42") (name "/PF11") (class "Default")
      (node (ref "R24") (pin "1") (pinfunction "1_1") (pintype "passive"))
      (node (ref "STM32F407ZET6") (pin "73") (pinfunction "PF11_73") (pintype "passive"))
    )
    (net (code "43") (name "/PF12") (class "Default")
      (node (ref "R25") (pin "2") (pinfunction "2_2") (pintype "passive"))
      (node (ref "STM32F407ZET6") (pin "74") (pinfunction "PF12_74") (pintype "passive"))
    )
    (net (code "44") (name "/PF13") (class "Default")
      (node (ref "R26") (pin "1") (pinfunction "1_1") (pintype "passive"))
      (node (ref "STM32F407ZET6") (pin "75") (pinfunction "PF13_75") (pintype "passive"))
    )
    (net (code "45") (name "/PF14") (class "Default")
      (node (ref "R27") (pin "2") (pinfunction "2_2") (pintype "passive"))
      (node (ref "STM32F407ZET6") (pin "76") (pinfunction "PF14_76") (pintype "passive"))
    )
    (net (code "46") (name "/PF15") (class "Default")
      (node (ref "R28") (pin "1") (pinfunction "1_1") (pintype "passive"))
      (node (ref "STM32F407ZET6") (pin "77") (pinfunction "PF15_77") (pintype "passive"))
    )
    (net (code "47") (name "/PG0") (class "Default")
      (node (ref "R29") (pin "2") (pinfunction "2_2") (pintype "passive"))
      (node (ref "STM32F407ZET6") (pin "78") (pinfunction "PG0_78") (pintype "passive"))
    )
    (net (code "48") (name "/PG1") (class "Default")
      (node (ref "R30") (pin "1") (pinfunction "1_1") (pintype "passive"))
      (node (ref "STM32F407ZET6") (pin "79") (pinfunction "PG1_79") (pintype "passive"))
    )
    (net (code "49") (name "/PG2") (class "Default")
      (node (ref "R31") (pin "2") (pinfunction "2_2") (pintype "passive"))
      (node (ref "STM32F407ZET6") (pin "105") (pinfunction "PG2_105") (pintype "passive"))
    )
    (net (code "50") (name "/PG3") (class "Default")
      (node (ref "R32") (pin "1") (pinfunction "1_1") (pintype "passive"))
      (node (ref "STM32F407ZET6") (pin "106") (pinfunction "PG3_106") (pintype "passive"))
    )
    (net (code "51") (name "/PG4") (class "Default")
      (node (ref "R33") (pin "2") (pinfunction "2_2") (pintype "passive"))
      (node (ref "STM32F407ZET6") (pin "107") (pinfunction "PG4_107") (pintype "passive"))
    )
    (net (code "52") (name "/PG5") (class "Default")
      (node (ref "R34") (pin "1") (pinfunction "1_1") (pintype "passive"))
      (node (ref "STM32F407ZET6") (pin "108") (pinfunction "PG5_108") (pintype "passive"))
    )
    (net (code "53") (name "/PG6") (class "Default")
      (node (ref "R35") (pin "2") (pinfunction "2_2") (pintype "passive"))
      (node (ref "STM32F407ZET6") (pin "109") (pinfunction "PG6_109") (pintype "passive"))
    )
    (net (code "54") (name "/PG7") (class "Default")
      (node (ref "R36") (pin "1") (pinfunction "1_1") (pintype "passive"))
      (node (ref "STM32F407ZET6") (pin "110") (pinfunction "PG7_110") (pintype "passive"))
    )
    (net (code "55") (name "/PG8") (class "Default")
      (node (ref "R37") (pin "2") (pinfunction "2_2") (pintype "passive"))
      (node (ref "STM32F407ZET6") (pin "111") (pinfunction "PG8_111") (pintype "passive"))
    )
    (net (code "56") (name "/PG10") (class "Default")
      (node (ref "R77") (pin "2") (pinfunction "2_2") (pintype "passive"))
      (node (ref "STM32F407ZET6") (pin "15") (pinfunction "PG10_15") (pintype "passive"))
    )
    (net (code "57") (name "/PG11") (class "Default")
      (node (ref "R78") (pin "1") (pinfunction "1_1") (pintype "passive"))
      (node (ref "STM32F407ZET6") (pin "16") (pinfunction "PG11_16") (pintype "passive"))
    )
    (net (code "58") (name "/PG12") (class "Default")
      (node (ref "R79") (pin "2") (pinfunction "2_2") (pintype "passive"))
      (node (ref "STM32F407ZET6") (pin "17") (pinfunction "PG12_17") (pintype "passive"))
    )
    (net (code "59") (name "/PG13") (class "Default")
      (node (ref "R80") (pin "1") (pinfunction "1_1") (pintype "passive"))
      (node (ref "STM32F407ZET6") (pin "18") (pinfunction "PG13_18") (pintype "passive"))
    )
    (net (code "60") (name "/PG15") (class "Default")
      (node (ref "R81") (pin "2") (pinfunction "2_2") (pintype "passive"))
      (node (ref "STM32F407ZET6") (pin "20") (pinfunction "PG15_20") (pintype "passive"))
    )
    (net (code "61") (name "/TIM1_CH1") (class "Default")
      (node (ref "R42") (pin "1") (pinfunction "1_1") (pintype "passive"))
      (node (ref "STM32F407ZET6") (pin "82") (pinfunction "PE9_82") (pintype "passive"))
    )
    (net (code "62") (name "/TIM1_CH2") (class "Default")
      (node (ref "R43") (pin "1") (pinfunction "1_1") (pintype "passive"))
      (node (ref "STM32F407ZET6") (pin "84") (pinfunction "PE11_84") (pintype "passive"))
    )
    (net (code "63") (name "/TIM1_CH3") (class "Default")
      (node (ref "R44") (pin "1") (pinfunction "1_1") (pintype "passive"))
      (node (ref "STM32F407ZET6") (pin "86") (pinfunction "PE13_86") (pintype "passive"))
    )
    (net (code "64") (name "/TIM1_CH4") (class "Default")
      (node (ref "R45") (pin "1") (pinfunction "1_1") (pintype "passive"))
      (node (ref "STM32F407ZET6") (pin "87") (pinfunction "PE14_87") (pintype "passive"))
    )
    (net (code "65") (name "/TIM2_CH1") (class "Default")
      (node (ref "R64") (pin "1") (pinfunction "1_1") (pintype "passive"))
      (node (ref "STM32F407ZET6") (pin "58") (pinfunction "PA0_58") (pintype "passive"))
    )
    (net (code "66") (name "/TIM2_CH2") (class "Default")
      (node (ref "R65") (pin "1") (pinfunction "1_1") (pintype "passive"))
      (node (ref "STM32F407ZET6") (pin "59") (pinfunction "PA1_59") (pintype "passive"))
    )
    (net (code "67") (name "/TIM2_CH3") (class "Default")
      (node (ref "R66") (pin "1") (pinfunction "1_1") (pintype "passive"))
      (node (ref "STM32F407ZET6") (pin "60") (pinfunction "PA2_60") (pintype "passive"))
    )
    (net (code "68") (name "/TIM2_CH4") (class "Default")
      (node (ref "R67") (pin "1") (pinfunction "1_1") (pintype "passive"))
      (node (ref "STM32F407ZET6") (pin "63") (pinfunction "PA3_63") (pintype "passive"))
    )
    (net (code "69") (name "/TIM3_CH1") (class "Default")
      (node (ref "R68") (pin "1") (pinfunction "1_1") (pintype "passive"))
      (node (ref "STM32F407ZET6") (pin "66") (pinfunction "PA6_66") (pintype "passive"))
    )
    (net (code "70") (name "/TIM3_CH2") (class "Default")
      (node (ref "R69") (pin "1") (pinfunction "1_1") (pintype "passive"))
      (node (ref "STM32F407ZET6") (pin "67") (pinfunction "PA7_67") (pintype "passive"))
    )
    (net (code "71") (name "/TIM3_CH3") (class "Default")
      (node (ref "R70") (pin "1") (pinfunction "1_1") (pintype "passive"))
      (node (ref "STM32F407ZET6") (pin "70") (pinfunction "PB0_70") (pintype "passive"))
    )
    (net (code "72") (name "/TIM3_CH4") (class "Default")
      (node (ref "R71") (pin "1") (pinfunction "1_1") (pintype "passive"))
      (node (ref "STM32F407ZET6") (pin "71") (pinfunction "PB1_71") (pintype "passive"))
    )
    (net (code "73") (name "/TIM4_CH1") (class "Default")
      (node (ref "R46") (pin "1") (pinfunction "1_1") (pintype "passive"))
      (node (ref "STM32F407ZET6") (pin "101") (pinfunction "PD12_101") (pintype "passive"))
    )
    (net (code "74") (name "/TIM4_CH2") (class "Default")
      (node (ref "R47") (pin "1") (pinfunction "1_1") (pintype "passive"))
      (node (ref "STM32F407ZET6") (pin "102") (pinfunction "PD13_102") (pintype "passive"))
    )
    (net (code "75") (name "/TIM4_CH3") (class "Default")
      (node (ref "R48") (pin "1") (pinfunction "1_1") (pintype "passive"))
      (node (ref "STM32F407ZET6") (pin "103") (pinfunction "PD14_103") (pintype "passive"))
    )
    (net (code "76") (name "/TIM4_CH4") (class "Default")
      (node (ref "R49") (pin "1") (pinfunction "1_1") (pintype "passive"))
      (node (ref "STM32F407ZET6") (pin "104") (pinfunction "PD15_104") (pintype "passive"))
    )
    (net (code "77") (name "/USART1_RX") (class "Default")
      (node (ref "P13") (pin "2") (pinfunction "2_2") (pintype "passive"))
      (node (ref "STM32F407ZET6") (pin "118") (pinfunction "PA10_118") (pintype "passive"))
    )
    (net (code "78") (name "/USART1_TX") (class "Default")
      (node (ref "P13") (pin "3") (pinfunction "3_3") (pintype "passive"))
      (node (ref "STM32F407ZET6") (pin "117") (pinfunction "PA9_117") (pintype "passive"))
    )
    (net (code "79") (name "/USART2_RX") (class "Default")
      (node (ref "P14") (pin "2") (pinfunction "2_2") (pintype "passive"))
      (node (ref "STM32F407ZET6") (pin "12") (pinfunction "PD6_12") (pintype "passive"))
    )
    (net (code "80") (name "/USART2_TX") (class "Default")
      (node (ref "P14") (pin "3") (pinfunction "3_3") (pintype "passive"))
      (node (ref "STM32F407ZET6") (pin "11") (pinfunction "PD5_11") (pintype "passive"))
    )
    (net (code "81") (name "/USART3_RX") (class "Default")
      (node (ref "P15") (pin "2") (pinfunction "2_2") (pintype "passive"))
      (node (ref "STM32F407ZET6") (pin "98") (pinfunction "PD9_98") (pintype "passive"))
    )
    (net (code "82") (name "/USART3_TX") (class "Default")
      (node (ref "P15") (pin "3") (pinfunction "3_3") (pintype "passive"))
      (node (ref "STM32F407ZET6") (pin "97") (pinfunction "PD8_97") (pintype "passive"))
    )
    (net (code "83") (name "/USART6_RX") (class "Default")
      (node (ref "J3") (pin "8") (pinfunction "8_8") (pintype "passive"))
      (node (ref "STM32F407ZET6") (pin "14") (pinfunction "PG9_14") (pintype "passive"))
    )
    (net (code "84") (name "/USART6_TX") (class "Default")
      (node (ref "J3") (pin "10") (pinfunction "10_10") (pintype "passive"))
      (node (ref "STM32F407ZET6") (pin "19") (pinfunction "PG14_19") (pintype "passive"))
    )
    (net (code "85") (name "GND") (class "Default")
      (node (ref "C1") (pin "1") (pinfunction "1_1") (pintype "passive"))
      (node (ref "C10") (pin "2") (pinfunction "2_2") (pintype "passive"))
      (node (ref "C12") (pin "1") (pinfunction "1_1") (pintype "passive"))
      (node (ref "C2") (pin "2") (pinfunction "2_2") (pintype "passive"))
      (node (ref "C3") (pin "2") (pinfunction "2_2") (pintype "passive"))
      (node (ref "C4") (pin "1") (pinfunction "1_1") (pintype "passive"))
      (node (ref "C5") (pin "1") (pinfunction "1_1") (pintype "passive"))
      (node (ref "C6") (pin "2") (pinfunction "2_2") (pintype "passive"))
      (node (ref "C7") (pin "2") (pinfunction "2_2") (pintype "passive"))
      (node (ref "C8") (pin "1") (pinfunction "1_1") (pintype "passive"))
      (node (ref "C9") (pin "2") (pinfunction "2_2") (pintype "passive"))
      (node (ref "D1") (pin "1") (pinfunction "A_1") (pintype "passive"))
      (node (ref "D2") (pin "2") (pinfunction "K_2") (pintype "passive"))
      (node (ref "D3") (pin "1") (pinfunction "A_1") (pintype "passive"))
      (node (ref "D4") (pin "2") (pinfunction "K_2") (pintype "passive"))
      (node (ref "J3") (pin "6") (pinfunction "6_6") (pintype "passive"))
      (node (ref "P11") (pin "10") (pinfunction "10_10") (pintype "passive"))
      (node (ref "P11") (pin "12") (pinfunction "12_12") (pintype "passive"))
      (node (ref "P11") (pin "14") (pinfunction "14_14") (pintype "passive"))
      (node (ref "P11") (pin "16") (pinfunction "16_16") (pintype "passive"))
      (node (ref "P11") (pin "2") (pinfunction "2_2") (pintype "passive"))
      (node (ref "P11") (pin "4") (pinfunction "4_4") (pintype "passive"))
      (node (ref "P11") (pin "6") (pinfunction "6_6") (pintype "passive"))
      (node (ref "P11") (pin "8") (pinfunction "8_8") (pintype "passive"))
      (node (ref "P12") (pin "20") (pinfunction "20_20") (pintype "passive"))
      (node (ref "P13") (pin "4") (pinfunction "4_4") (pintype "passive"))
      (node (ref "P14") (pin "4") (pinfunction "4_4") (pintype "passive"))
      (node (ref "P15") (pin "4") (pinfunction "4_4") (pintype "passive"))
      (node (ref "P16") (pin "11") (pinfunction "11_11") (pintype "passive"))
      (node (ref "P16") (pin "12") (pinfunction "12_12") (pintype "passive"))
      (node (ref "P17") (pin "8") (pinfunction "8_8") (pintype "passive"))
      (node (ref "P19") (pin "10") (pinfunction "10_10") (pintype "passive"))
      (node (ref "P19") (pin "12") (pinfunction "12_12") (pintype "passive"))
      (node (ref "P19") (pin "14") (pinfunction "14_14") (pintype "passive"))
      (node (ref "P19") (pin "16") (pinfunction "16_16") (pintype "passive"))
      (node (ref "P19") (pin "18") (pinfunction "18_18") (pintype "passive"))
      (node (ref "P19") (pin "2") (pinfunction "2_2") (pintype "passive"))
      (node (ref "P19") (pin "20") (pinfunction "20_20") (pintype "passive"))
      (node (ref "P19") (pin "22") (pinfunction "22_22") (pintype "passive"))
      (node (ref "P19") (pin "24") (pinfunction "24_24") (pintype "passive"))
      (node (ref "P19") (pin "26") (pinfunction "26_26") (pintype "passive"))
      (node (ref "P19") (pin "28") (pinfunction "28_28") (pintype "passive"))
      (node (ref "P19") (pin "4") (pinfunction "4_4") (pintype "passive"))
      (node (ref "P19") (pin "6") (pinfunction "6_6") (pintype "passive"))
      (node (ref "P19") (pin "8") (pinfunction "8_8") (pintype "passive"))
      (node (ref "P9") (pin "10") (pinfunction "10_10") (pintype "passive"))
      (node (ref "P9") (pin "12") (pinfunction "12_12") (pintype "passive"))
      (node (ref "P9") (pin "14") (pinfunction "14_14") (pintype "passive"))
      (node (ref "P9") (pin "16") (pinfunction "16_16") (pintype "passive"))
      (node (ref "P9") (pin "2") (pinfunction "2_2") (pintype "passive"))
      (node (ref "P9") (pin "4") (pinfunction "4_4") (pintype "passive"))
      (node (ref "P9") (pin "6") (pinfunction "6_6") (pintype "passive"))
      (node (ref "P9") (pin "8") (pinfunction "8_8") (pintype "passive"))
      (node (ref "R1") (pin "1") (pinfunction "1_1") (pintype "passive"))
      (node (ref "R10") (pin "1") (pinfunction "1_1") (pintype "passive"))
      (node (ref "R4") (pin "1") (pinfunction "1_1") (pintype "passive"))
      (node (ref "STM32F407ZET6") (pin "122") (pinfunction "GND_122") (pintype "passive"))
      (node (ref "STM32F407ZET6") (pin "124") (pinfunction "GND_124") (pintype "passive"))
      (node (ref "STM32F407ZET6") (pin "56") (pinfunction "V-_56") (pintype "passive"))
      (node (ref "U2") (pin "2") (pinfunction "VSS_2") (pintype "passive"))
      (node (ref "U2") (pin "8") (pinfunction "STBY_8") (pintype "passive"))
      (node (ref "U3") (pin "2") (pinfunction "VSS_2") (pintype "passive"))
      (node (ref "U3") (pin "8") (pinfunction "STBY_8") (pintype "passive"))
      (node (ref "U4") (pin "3") (pinfunction "COMMON_3") (pintype "power_in"))
      (node (ref "U4") (pin "5") (pinfunction "ON/OFF_5") (pintype "passive"))
      (node (ref "U5") (pin "3") (pinfunction "COMMON_3") (pintype "power_in"))
      (node (ref "U5") (pin "5") (pinfunction "ON/OFF_5") (pintype "passive"))
      (node (ref "X0") (pin "2") (pinfunction "2_2") (pintype "passive"))
      (node (ref "X1") (pin "2") (pinfunction "2_2") (pintype "passive"))
      (node (ref "X2") (pin "2") (pinfunction "2_2") (pintype "passive"))
      (node (ref "X3") (pin "2") (pinfunction "2_2") (pintype "passive"))
      (node (ref "X4") (pin "2") (pinfunction "2_2") (pintype "passive"))
      (node (ref "X5") (pin "2") (pinfunction "2_2") (pintype "passive"))
      (node (ref "X6") (pin "2") (pinfunction "2_2") (pintype "passive"))
      (node (ref "X7") (pin "2") (pinfunction "2_2") (pintype "passive"))
    )
    (net (code "86") (name "Net-(D1-K)") (class "Default")
      (node (ref "D1") (pin "2") (pinfunction "K_2") (pintype "passive"))
      (node (ref "L1") (pin "1") (pinfunction "1_1") (pintype "passive"))
      (node (ref "U4") (pin "2") (pinfunction "OUT_2") (pintype "passive"))
    )
    (net (code "87") (name "Net-(D2-A)") (class "Default")
      (node (ref "D2") (pin "1") (pinfunction "A_1") (pintype "passive"))
      (node (ref "R3") (pin "2") (pinfunction "2_2") (pintype "passive"))
    )
    (net (code "88") (name "Net-(D3-K)") (class "Default")
      (node (ref "D3") (pin "2") (pinfunction "K_2") (pintype "passive"))
      (node (ref "L2") (pin "1") (pinfunction "1_1") (pintype "passive"))
      (node (ref "U5") (pin "2") (pinfunction "OUT_2") (pintype "passive"))
    )
    (net (code "89") (name "Net-(D4-A)") (class "Default")
      (node (ref "D4") (pin "1") (pinfunction "A_1") (pintype "passive"))
      (node (ref "R6") (pin "2") (pinfunction "2_2") (pintype "passive"))
    )
    (net (code "90") (name "Net-(P8-Pad1)") (class "Default")
      (node (ref "P8") (pin "1") (pinfunction "1_1") (pintype "passive"))
      (node (ref "R64") (pin "2") (pinfunction "2_2") (pintype "passive"))
    )
    (net (code "91") (name "Net-(P8-Pad2)") (class "Default")
      (node (ref "P8") (pin "2") (pinfunction "2_2") (pintype "passive"))
      (node (ref "R65") (pin "2") (pinfunction "2_2") (pintype "passive"))
    )
    (net (code "92") (name "Net-(P8-Pad3)") (class "Default")
      (node (ref "P8") (pin "3") (pinfunction "3_3") (pintype "passive"))
      (node (ref "R66") (pin "2") (pinfunction "2_2") (pintype "passive"))
    )
    (net (code "93") (name "Net-(P8-Pad4)") (class "Default")
      (node (ref "P8") (pin "4") (pinfunction "4_4") (pintype "passive"))
      (node (ref "R67") (pin "2") (pinfunction "2_2") (pintype "passive"))
    )
    (net (code "94") (name "Net-(P8-Pad5)") (class "Default")
      (node (ref "P8") (pin "5") (pinfunction "5_5") (pintype "passive"))
      (node (ref "R68") (pin "2") (pinfunction "2_2") (pintype "passive"))
    )
    (net (code "95") (name "Net-(P8-Pad6)") (class "Default")
      (node (ref "P8") (pin "6") (pinfunction "6_6") (pintype "passive"))
      (node (ref "R69") (pin "2") (pinfunction "2_2") (pintype "passive"))
    )
    (net (code "96") (name "Net-(P8-Pad7)") (class "Default")
      (node (ref "P8") (pin "7") (pinfunction "7_7") (pintype "passive"))
      (node (ref "R70") (pin "2") (pinfunction "2_2") (pintype "passive"))
    )
    (net (code "97") (name "Net-(P8-Pad8)") (class "Default")
      (node (ref "P8") (pin "8") (pinfunction "8_8") (pintype "passive"))
      (node (ref "R71") (pin "2") (pinfunction "2_2") (pintype "passive"))
    )
    (net (code "98") (name "Net-(P10-Pad1)") (class "Default")
      (node (ref "P10") (pin "1") (pinfunction "1_1") (pintype "passive"))
      (node (ref "R42") (pin "2") (pinfunction "2_2") (pintype "passive"))
    )
    (net (code "99") (name "Net-(P10-Pad2)") (class "Default")
      (node (ref "P10") (pin "2") (pinfunction "2_2") (pintype "passive"))
      (node (ref "R43") (pin "2") (pinfunction "2_2") (pintype "passive"))
    )
    (net (code "100") (name "Net-(P10-Pad3)") (class "Default")
      (node (ref "P10") (pin "3") (pinfunction "3_3") (pintype "passive"))
      (node (ref "R44") (pin "2") (pinfunction "2_2") (pintype "passive"))
    )
    (net (code "101") (name "Net-(P10-Pad4)") (class "Default")
      (node (ref "P10") (pin "4") (pinfunction "4_4") (pintype "passive"))
      (node (ref "R45") (pin "2") (pinfunction "2_2") (pintype "passive"))
    )
    (net (code "102") (name "Net-(P10-Pad5)") (class "Default")
      (node (ref "P10") (pin "5") (pinfunction "5_5") (pintype "passive"))
      (node (ref "R46") (pin "2") (pinfunction "2_2") (pintype "passive"))
    )
    (net (code "103") (name "Net-(P10-Pad6)") (class "Default")
      (node (ref "P10") (pin "6") (pinfunction "6_6") (pintype "passive"))
      (node (ref "R47") (pin "2") (pinfunction "2_2") (pintype "passive"))
    )
    (net (code "104") (name "Net-(P10-Pad7)") (class "Default")
      (node (ref "P10") (pin "7") (pinfunction "7_7") (pintype "passive"))
      (node (ref "R48") (pin "2") (pinfunction "2_2") (pintype "passive"))
    )
    (net (code "105") (name "Net-(P10-Pad8)") (class "Default")
      (node (ref "P10") (pin "8") (pinfunction "8_8") (pintype "passive"))
      (node (ref "R49") (pin "2") (pinfunction "2_2") (pintype "passive"))
    )
    (net (code "106") (name "Net-(P12-Pad1)") (class "Default")
      (node (ref "P12") (pin "1") (pinfunction "1_1") (pintype "passive"))
      (node (ref "R24") (pin "2") (pinfunction "2_2") (pintype "passive"))
    )
    (net (code "107") (name "Net-(P12-Pad2)") (class "Default")
      (node (ref "P12") (pin "2") (pinfunction "2_2") (pintype "passive"))
      (node (ref "R25") (pin "1") (pinfunction "1_1") (pintype "passive"))
    )
    (net (code "108") (name "Net-(P12-Pad3)") (class "Default")
      (node (ref "P12") (pin "3") (pinfunction "3_3") (pintype "passive"))
      (node (ref "R26") (pin "2") (pinfunction "2_2") (pintype "passive"))
    )
    (net (code "109") (name "Net-(P12-Pad4)") (class "Default")
      (node (ref "P12") (pin "4") (pinfunction "4_4") (pintype "passive"))
      (node (ref "R27") (pin "1") (pinfunction "1_1") (pintype "passive"))
    )
    (net (code "110") (name "Net-(P12-Pad5)") (class "Default")
      (node (ref "P12") (pin "5") (pinfunction "5_5") (pintype "passive"))
      (node (ref "R28") (pin "2") (pinfunction "2_2") (pintype "passive"))
    )
    (net (code "111") (name "Net-(P12-Pad6)") (class "Default")
      (node (ref "P12") (pin "6") (pinfunction "6_6") (pintype "passive"))
      (node (ref "R29") (pin "1") (pinfunction "1_1") (pintype "passive"))
    )
    (net (code "112") (name "Net-(P12-Pad7)") (class "Default")
      (node (ref "P12") (pin "7") (pinfunction "7_7") (pintype "passive"))
      (node (ref "R30") (pin "2") (pinfunction "2_2") (pintype "passive"))
    )
    (net (code "113") (name "Net-(P12-Pad8)") (class "Default")
      (node (ref "P12") (pin "8") (pinfunction "8_8") (pintype "passive"))
      (node (ref "R31") (pin "1") (pinfunction "1_1") (pintype "passive"))
    )
    (net (code "114") (name "Net-(P12-Pad9)") (class "Default")
      (node (ref "P12") (pin "9") (pinfunction "9_9") (pintype "passive"))
      (node (ref "R32") (pin "2") (pinfunction "2_2") (pintype "passive"))
    )
    (net (code "115") (name "Net-(P12-Pad10)") (class "Default")
      (node (ref "P12") (pin "10") (pinfunction "10_10") (pintype "passive"))
      (node (ref "R33") (pin "1") (pinfunction "1_1") (pintype "passive"))
    )
    (net (code "116") (name "Net-(P12-Pad11)") (class "Default")
      (node (ref "P12") (pin "11") (pinfunction "11_11") (pintype "passive"))
      (node (ref "R34") (pin "2") (pinfunction "2_2") (pintype "passive"))
    )
    (net (code "117") (name "Net-(P12-Pad12)") (class "Default")
      (node (ref "P12") (pin "12") (pinfunction "12_12") (pintype "passive"))
      (node (ref "R35") (pin "1") (pinfunction "1_1") (pintype "passive"))
    )
    (net (code "118") (name "Net-(P12-Pad13)") (class "Default")
      (node (ref "P12") (pin "13") (pinfunction "13_13") (pintype "passive"))
      (node (ref "R36") (pin "2") (pinfunction "2_2") (pintype "passive"))
    )
    (net (code "119") (name "Net-(P12-Pad14)") (class "Default")
      (node (ref "P12") (pin "14") (pinfunction "14_14") (pintype "passive"))
      (node (ref "R37") (pin "1") (pinfunction "1_1") (pintype "passive"))
    )
    (net (code "120") (name "Net-(P12-Pad15)") (class "Default")
      (node (ref "P12") (pin "15") (pinfunction "15_15") (pintype "passive"))
      (node (ref "R38") (pin "2") (pinfunction "2_2") (pintype "passive"))
    )
    (net (code "121") (name "Net-(P12-Pad16)") (class "Default")
      (node (ref "P12") (pin "16") (pinfunction "16_16") (pintype "passive"))
      (node (ref "R39") (pin "1") (pinfunction "1_1") (pintype "passive"))
    )
    (net (code "122") (name "Net-(P12-Pad17)") (class "Default")
      (node (ref "P12") (pin "17") (pinfunction "17_17") (pintype "passive"))
      (node (ref "R40") (pin "2") (pinfunction "2_2") (pintype "passive"))
    )
    (net (code "123") (name "Net-(P12-Pad18)") (class "Default")
      (node (ref "P12") (pin "18") (pinfunction "18_18") (pintype "passive"))
      (node (ref "R41") (pin "1") (pinfunction "1_1") (pintype "passive"))
    )
    (net (code "124") (name "Net-(P16-Pad1)") (class "Default")
      (node (ref "P16") (pin "1") (pinfunction "1_1") (pintype "passive"))
      (node (ref "R11") (pin "2") (pinfunction "2_2") (pintype "passive"))
    )
    (net (code "125") (name "Net-(P16-Pad2)") (class "Default")
      (node (ref "P16") (pin "2") (pinfunction "2_2") (pintype "passive"))
      (node (ref "R12") (pin "1") (pinfunction "1_1") (pintype "passive"))
    )
    (net (code "126") (name "Net-(P16-Pad3)") (class "Default")
      (node (ref "P16") (pin "3") (pinfunction "3_3") (pintype "passive"))
      (node (ref "R13") (pin "2") (pinfunction "2_2") (pintype "passive"))
    )
    (net (code "127") (name "Net-(P16-Pad4)") (class "Default")
      (node (ref "P16") (pin "4") (pinfunction "4_4") (pintype "passive"))
      (node (ref "R14") (pin "1") (pinfunction "1_1") (pintype "passive"))
    )
    (net (code "128") (name "Net-(P16-Pad5)") (class "Default")
      (node (ref "P16") (pin "5") (pinfunction "5_5") (pintype "passive"))
      (node (ref "R15") (pin "2") (pinfunction "2_2") (pintype "passive"))
    )
    (net (code "129") (name "Net-(P16-Pad6)") (class "Default")
      (node (ref "P16") (pin "6") (pinfunction "6_6") (pintype "passive"))
      (node (ref "R16") (pin "1") (pinfunction "1_1") (pintype "passive"))
    )
    (net (code "130") (name "Net-(P16-Pad7)") (class "Default")
      (node (ref "P16") (pin "7") (pinfunction "7_7") (pintype "passive"))
      (node (ref "R17") (pin "2") (pinfunction "2_2") (pintype "passive"))
    )
    (net (code "131") (name "Net-(P16-Pad8)") (class "Default")
      (node (ref "P16") (pin "8") (pinfunction "8_8") (pintype "passive"))
      (node (ref "R18") (pin "1") (pinfunction "1_1") (pintype "passive"))
    )
    (net (code "132") (name "Net-(P17-Pad1)") (class "Default")
      (node (ref "P17") (pin "1") (pinfunction "1_1") (pintype "passive"))
      (node (ref "R19") (pin "2") (pinfunction "2_2") (pintype "passive"))
    )
    (net (code "133") (name "Net-(P17-Pad2)") (class "Default")
      (node (ref "P17") (pin "2") (pinfunction "2_2") (pintype "passive"))
      (node (ref "R20") (pin "1") (pinfunction "1_1") (pintype "passive"))
    )
    (net (code "134") (name "Net-(P17-Pad3)") (class "Default")
      (node (ref "P17") (pin "3") (pinfunction "3_3") (pintype "passive"))
      (node (ref "R21") (pin "2") (pinfunction "2_2") (pintype "passive"))
    )
    (net (code "135") (name "Net-(P17-Pad4)") (class "Default")
      (node (ref "P17") (pin "4") (pinfunction "4_4") (pintype "passive"))
      (node (ref "R22") (pin "1") (pinfunction "1_1") (pintype "passive"))
    )
    (net (code "136") (name "Net-(P17-Pad5)") (class "Default")
      (node (ref "P17") (pin "5") (pinfunction "5_5") (pintype "passive"))
      (node (ref "R23") (pin "2") (pinfunction "2_2") (pintype "passive"))
    )
    (net (code "137") (name "Net-(P18-Pad1)") (class "Default")
      (node (ref "P18") (pin "1") (pinfunction "1_1") (pintype "passive"))
      (node (ref "R50") (pin "2") (pinfunction "2_2") (pintype "passive"))
    )
    (net (code "138") (name "Net-(P18-Pad2)") (class "Default")
      (node (ref "P18") (pin "2") (pinfunction "2_2") (pintype "passive"))
      (node (ref "R51") (pin "2") (pinfunction "2_2") (pintype "passive"))
    )
    (net (code "139") (name "Net-(P18-Pad3)") (class "Default")
      (node (ref "P18") (pin "3") (pinfunction "3_3") (pintype "passive"))
      (node (ref "R52") (pin "2") (pinfunction "2_2") (pintype "passive"))
    )
    (net (code "140") (name "Net-(P18-Pad4)") (class "Default")
      (node (ref "P18") (pin "4") (pinfunction "4_4") (pintype "passive"))
      (node (ref "R53") (pin "2") (pinfunction "2_2") (pintype "passive"))
    )
    (net (code "141") (name "Net-(P18-Pad5)") (class "Default")
      (node (ref "P18") (pin "5") (pinfunction "5_5") (pintype "passive"))
      (node (ref "R54") (pin "2") (pinfunction "2_2") (pintype "passive"))
    )
    (net (code "142") (name "Net-(P18-Pad6)") (class "Default")
      (node (ref "P18") (pin "6") (pinfunction "6_6") (pintype "passive"))
      (node (ref "R55") (pin "2") (pinfunction "2_2") (pintype "passive"))
    )
    (net (code "143") (name "Net-(P18-Pad7)") (class "Default")
      (node (ref "P18") (pin "7") (pinfunction "7_7") (pintype "passive"))
      (node (ref "R56") (pin "2") (pinfunction "2_2") (pintype "passive"))
    )
    (net (code "144") (name "Net-(P18-Pad8)") (class "Default")
      (node (ref "P18") (pin "8") (pinfunction "8_8") (pintype "passive"))
      (node (ref "R57") (pin "2") (pinfunction "2_2") (pintype "passive"))
    )
    (net (code "145") (name "Net-(P18-Pad9)") (class "Default")
      (node (ref "P18") (pin "9") (pinfunction "9_9") (pintype "passive"))
      (node (ref "R58") (pin "2") (pinfunction "2_2") (pintype "passive"))
    )
    (net (code "146") (name "Net-(P18-Pad10)") (class "Default")
      (node (ref "P18") (pin "10") (pinfunction "10_10") (pintype "passive"))
      (node (ref "R59") (pin "2") (pinfunction "2_2") (pintype "passive"))
    )
    (net (code "147") (name "Net-(P18-Pad11)") (class "Default")
      (node (ref "P18") (pin "11") (pinfunction "11_11") (pintype "passive"))
      (node (ref "R60") (pin "2") (pinfunction "2_2") (pintype "passive"))
    )
    (net (code "148") (name "Net-(P18-Pad12)") (class "Default")
      (node (ref "P18") (pin "12") (pinfunction "12_12") (pintype "passive"))
      (node (ref "R61") (pin "2") (pinfunction "2_2") (pintype "passive"))
    )
    (net (code "149") (name "Net-(P18-Pad13)") (class "Default")
      (node (ref "P18") (pin "13") (pinfunction "13_13") (pintype "passive"))
      (node (ref "R62") (pin "2") (pinfunction "2_2") (pintype "passive"))
    )
    (net (code "150") (name "Net-(P18-Pad14)") (class "Default")
      (node (ref "P18") (pin "14") (pinfunction "14_14") (pintype "passive"))
      (node (ref "R63") (pin "2") (pinfunction "2_2") (pintype "passive"))
    )
    (net (code "151") (name "Net-(P20-Pad1)") (class "Default")
      (node (ref "P20") (pin "1") (pinfunction "1_1") (pintype "passive"))
      (node (ref "R72") (pin "2") (pinfunction "2_2") (pintype "passive"))
    )
    (net (code "152") (name "Net-(P20-Pad2)") (class "Default")
      (node (ref "P20") (pin "2") (pinfunction "2_2") (pintype "passive"))
      (node (ref "R73") (pin "1") (pinfunction "1_1") (pintype "passive"))
    )
    (net (code "153") (name "Net-(P20-Pad3)") (class "Default")
      (node (ref "P20") (pin "3") (pinfunction "3_3") (pintype "passive"))
      (node (ref "R74") (pin "2") (pinfunction "2_2") (pintype "passive"))
    )
    (net (code "154") (name "Net-(P20-Pad4)") (class "Default")
      (node (ref "P20") (pin "4") (pinfunction "4_4") (pintype "passive"))
      (node (ref "R75") (pin "1") (pinfunction "1_1") (pintype "passive"))
    )
    (net (code "155") (name "Net-(P20-Pad5)") (class "Default")
      (node (ref "P20") (pin "5") (pinfunction "5_5") (pintype "passive"))
      (node (ref "R76") (pin "2") (pinfunction "2_2") (pintype "passive"))
    )
    (net (code "156") (name "Net-(P20-Pad6)") (class "Default")
      (node (ref "P20") (pin "6") (pinfunction "6_6") (pintype "passive"))
      (node (ref "R77") (pin "1") (pinfunction "1_1") (pintype "passive"))
    )
    (net (code "157") (name "Net-(P20-Pad7)") (class "Default")
      (node (ref "P20") (pin "7") (pinfunction "7_7") (pintype "passive"))
      (node (ref "R78") (pin "2") (pinfunction "2_2") (pintype "passive"))
    )
    (net (code "158") (name "Net-(P20-Pad8)") (class "Default")
      (node (ref "P20") (pin "8") (pinfunction "8_8") (pintype "passive"))
      (node (ref "R79") (pin "1") (pinfunction "1_1") (pintype "passive"))
    )
    (net (code "159") (name "Net-(P20-Pad9)") (class "Default")
      (node (ref "P20") (pin "9") (pinfunction "9_9") (pintype "passive"))
      (node (ref "R80") (pin "2") (pinfunction "2_2") (pintype "passive"))
    )
    (net (code "160") (name "Net-(P20-Pad10)") (class "Default")
      (node (ref "P20") (pin "10") (pinfunction "10_10") (pintype "passive"))
      (node (ref "R81") (pin "1") (pinfunction "1_1") (pintype "passive"))
    )
    (net (code "161") (name "Net-(R2-A)") (class "Default")
      (node (ref "R1") (pin "2") (pinfunction "2_2") (pintype "passive"))
      (node (ref "R2") (pin "1") (pinfunction "A_1") (pintype "passive"))
      (node (ref "U4") (pin "4") (pinfunction "FB_4") (pintype "passive"))
    )
    (net (code "162") (name "Net-(R5-A)") (class "Default")
      (node (ref "R4") (pin "2") (pinfunction "2_2") (pintype "passive"))
      (node (ref "R5") (pin "1") (pinfunction "A_1") (pintype "passive"))
      (node (ref "U5") (pin "4") (pinfunction "FB_4") (pintype "passive"))
    )
    (net (code "163") (name "Net-(U2-CANH)") (class "Default")
      (node (ref "P1") (pin "1") (pinfunction "1_1") (pintype "passive"))
      (node (ref "P2") (pin "1") (pinfunction "1_1") (pintype "passive"))
      (node (ref "P3") (pin "1") (pinfunction "1_1") (pintype "passive"))
      (node (ref "P4") (pin "1") (pinfunction "1_1") (pintype "passive"))
      (node (ref "P5") (pin "1") (pinfunction "1_1") (pintype "passive"))
      (node (ref "P6") (pin "1") (pinfunction "1_1") (pintype "passive"))
      (node (ref "R7") (pin "2") (pinfunction "2_2") (pintype "passive"))
      (node (ref "U2") (pin "7") (pinfunction "CANH_7") (pintype "passive"))
    )
    (net (code "164") (name "Net-(U2-CANL)") (class "Default")
      (node (ref "P1") (pin "2") (pinfunction "2_2") (pintype "passive"))
      (node (ref "P2") (pin "2") (pinfunction "2_2") (pintype "passive"))
      (node (ref "P3") (pin "2") (pinfunction "2_2") (pintype "passive"))
      (node (ref "P4") (pin "2") (pinfunction "2_2") (pintype "passive"))
      (node (ref "P5") (pin "2") (pinfunction "2_2") (pintype "passive"))
      (node (ref "P6") (pin "2") (pinfunction "2_2") (pintype "passive"))
      (node (ref "R7") (pin "1") (pinfunction "1_1") (pintype "passive"))
      (node (ref "U2") (pin "6") (pinfunction "CANL_6") (pintype "passive"))
    )
    (net (code "165") (name "Net-(U3-CANH)") (class "Default")
      (node (ref "P7") (pin "1") (pinfunction "1_1") (pintype "passive"))
      (node (ref "R8") (pin "2") (pinfunction "2_2") (pintype "passive"))
      (node (ref "U3") (pin "7") (pinfunction "CANH_7") (pintype "passive"))
    )
    (net (code "166") (name "Net-(U3-CANL)") (class "Default")
      (node (ref "P7") (pin "2") (pinfunction "2_2") (pintype "passive"))
      (node (ref "R8") (pin "1") (pinfunction "1_1") (pintype "passive"))
      (node (ref "U3") (pin "6") (pinfunction "CANL_6") (pintype "passive"))
    )
    (net (code "167") (name "VCC_3V3") (class "Default")
      (node (ref "P16") (pin "9") (pinfunction "9_9") (pintype "passive"))
      (node (ref "P17") (pin "7") (pinfunction "7_7") (pintype "passive"))
      (node (ref "STM32F407ZET6") (pin "123") (pinfunction "3.3V_123") (pintype "passive"))
      (node (ref "STM32F407ZET6") (pin "57") (pinfunction "V+_57") (pintype "passive"))
      (node (ref "U2") (pin "5") (pinfunction "VIO_5") (pintype "passive"))
      (node (ref "U3") (pin "5") (pinfunction "VIO_5") (pintype "passive"))
    )
    (net (code "168") (name "VCC_5V") (class "Default")
      (node (ref "C10") (pin "1") (pinfunction "1_1") (pintype "passive"))
      (node (ref "C7") (pin "1") (pinfunction "1_1") (pintype "passive"))
      (node (ref "C8") (pin "2") (pinfunction "2_2") (pintype "passive"))
      (node (ref "C9") (pin "1") (pinfunction "1_1") (pintype "passive"))
      (node (ref "J3") (pin "2") (pinfunction "2_2") (pintype "passive"))
      (node (ref "L2") (pin "2") (pinfunction "2_2") (pintype "passive"))
      (node (ref "P11") (pin "1") (pinfunction "1_1") (pintype "passive"))
      (node (ref "P11") (pin "11") (pinfunction "11_11") (pintype "passive"))
      (node (ref "P11") (pin "13") (pinfunction "13_13") (pintype "passive"))
      (node (ref "P11") (pin "15") (pinfunction "15_15") (pintype "passive"))
      (node (ref "P11") (pin "3") (pinfunction "3_3") (pintype "passive"))
      (node (ref "P11") (pin "5") (pinfunction "5_5") (pintype "passive"))
      (node (ref "P11") (pin "7") (pinfunction "7_7") (pintype "passive"))
      (node (ref "P11") (pin "9") (pinfunction "9_9") (pintype "passive"))
      (node (ref "P12") (pin "19") (pinfunction "19_19") (pintype "passive"))
      (node (ref "P13") (pin "1") (pinfunction "1_1") (pintype "passive"))
      (node (ref "P14") (pin "1") (pinfunction "1_1") (pintype "passive"))
      (node (ref "P15") (pin "1") (pinfunction "1_1") (pintype "passive"))
      (node (ref "P16") (pin "10") (pinfunction "10_10") (pintype "passive"))
      (node (ref "P17") (pin "6") (pinfunction "6_6") (pintype "passive"))
      (node (ref "P19") (pin "1") (pinfunction "1_1") (pintype "passive"))
      (node (ref "P19") (pin "11") (pinfunction "11_11") (pintype "passive"))
      (node (ref "P19") (pin "13") (pinfunction "13_13") (pintype "passive"))
      (node (ref "P19") (pin "15") (pinfunction "15_15") (pintype "passive"))
      (node (ref "P19") (pin "17") (pinfunction "17_17") (pintype "passive"))
      (node (ref "P19") (pin "19") (pinfunction "19_19") (pintype "passive"))
      (node (ref "P19") (pin "21") (pinfunction "21_21") (pintype "passive"))
      (node (ref "P19") (pin "23") (pinfunction "23_23") (pintype "passive"))
      (node (ref "P19") (pin "25") (pinfunction "25_25") (pintype "passive"))
      (node (ref "P19") (pin "27") (pinfunction "27_27") (pintype "passive"))
      (node (ref "P19") (pin "3") (pinfunction "3_3") (pintype "passive"))
      (node (ref "P19") (pin "5") (pinfunction "5_5") (pintype "passive"))
      (node (ref "P19") (pin "7") (pinfunction "7_7") (pintype "passive"))
      (node (ref "P19") (pin "9") (pinfunction "9_9") (pintype "passive"))
      (node (ref "R5") (pin "2") (pinfunction "B_2") (pintype "passive"))
      (node (ref "R5") (pin "3") (pinfunction "TAP_3") (pintype "passive"))
      (node (ref "R6") (pin "1") (pinfunction "1_1") (pintype "passive"))
      (node (ref "STM32F407ZET6") (pin "30") (pinfunction "5V_30") (pintype "passive"))
      (node (ref "STM32F407ZET6") (pin "61") (pinfunction "5V_61") (pintype "passive"))
      (node (ref "U2") (pin "3") (pinfunction "VDD_3") (pintype "passive"))
      (node (ref "U3") (pin "3") (pinfunction "VDD_3") (pintype "passive"))
    )
    (net (code "169") (name "VCC_24V") (class "Default")
      (node (ref "C1") (pin "2") (pinfunction "2_2") (pintype "passive"))
      (node (ref "C11") (pin "2") (pinfunction "2_2") (pintype "passive"))
      (node (ref "C2") (pin "1") (pinfunction "1_1") (pintype "passive"))
      (node (ref "C5") (pin "2") (pinfunction "2_2") (pintype "passive"))
      (node (ref "C6") (pin "1") (pinfunction "1_1") (pintype "passive"))
      (node (ref "R9") (pin "2") (pinfunction "2_2") (pintype "passive"))
      (node (ref "U4") (pin "1") (pinfunction "VIN_1") (pintype "passive"))
      (node (ref "U5") (pin "1") (pinfunction "VIN_1") (pintype "passive"))
      (node (ref "X0") (pin "1") (pinfunction "1_1") (pintype "passive"))
      (node (ref "X1") (pin "1") (pinfunction "1_1") (pintype "passive"))
      (node (ref "X2") (pin "1") (pinfunction "1_1") (pintype "passive"))
      (node (ref "X3") (pin "1") (pinfunction "1_1") (pintype "passive"))
      (node (ref "X4") (pin "1") (pinfunction "1_1") (pintype "passive"))
      (node (ref "X5") (pin "1") (pinfunction "1_1") (pintype "passive"))
      (node (ref "X6") (pin "1") (pinfunction "1_1") (pintype "passive"))
      (node (ref "X7") (pin "1") (pinfunction "1_1") (pintype "passive"))
    )
    (net (code "170") (name "VCC_ADJ") (class "Default")
      (node (ref "C3") (pin "1") (pinfunction "1_1") (pintype "passive"))
      (node (ref "C4") (pin "2") (pinfunction "2_2") (pintype "passive"))
      (node (ref "L1") (pin "2") (pinfunction "2_2") (pintype "passive"))
      (node (ref "P9") (pin "1") (pinfunction "1_1") (pintype "passive"))
      (node (ref "P9") (pin "11") (pinfunction "11_11") (pintype "passive"))
      (node (ref "P9") (pin "13") (pinfunction "13_13") (pintype "passive"))
      (node (ref "P9") (pin "15") (pinfunction "15_15") (pintype "passive"))
      (node (ref "P9") (pin "3") (pinfunction "3_3") (pintype "passive"))
      (node (ref "P9") (pin "5") (pinfunction "5_5") (pintype "passive"))
      (node (ref "P9") (pin "7") (pinfunction "7_7") (pintype "passive"))
      (node (ref "P9") (pin "9") (pinfunction "9_9") (pintype "passive"))
      (node (ref "R2") (pin "2") (pinfunction "B_2") (pintype "passive"))
      (node (ref "R2") (pin "3") (pinfunction "TAP_3") (pintype "passive"))
      (node (ref "R3") (pin "1") (pinfunction "1_1") (pintype "passive"))
    )
    (net (code "171") (name "unconnected-(J3-Pad1)") (class "Default")
      (node (ref "J3") (pin "1") (pinfunction "1_1") (pintype "passive"))
    )
    (net (code "172") (name "unconnected-(J3-Pad3)") (class "Default")
      (node (ref "J3") (pin "3") (pinfunction "3_3") (pintype "passive"))
    )
    (net (code "173") (name "unconnected-(J3-Pad4)") (class "Default")
      (node (ref "J3") (pin "4") (pinfunction "4_4") (pintype "passive"))
    )
    (net (code "174") (name "unconnected-(J3-Pad5)") (class "Default")
      (node (ref "J3") (pin "5") (pinfunction "5_5") (pintype "passive"))
    )
    (net (code "175") (name "unconnected-(J3-Pad7)") (class "Default")
      (node (ref "J3") (pin "7") (pinfunction "7_7") (pintype "passive"))
    )
    (net (code "176") (name "unconnected-(J3-Pad9)") (class "Default")
      (node (ref "J3") (pin "9") (pinfunction "9_9") (pintype "passive"))
    )
    (net (code "177") (name "unconnected-(J3-Pad11)") (class "Default")
      (node (ref "J3") (pin "11") (pinfunction "11_11") (pintype "passive"))
    )
    (net (code "178") (name "unconnected-(J3-Pad12)") (class "Default")
      (node (ref "J3") (pin "12") (pinfunction "12_12") (pintype "passive"))
    )
    (net (code "179") (name "unconnected-(J3-Pad13)") (class "Default")
      (node (ref "J3") (pin "13") (pinfunction "13_13") (pintype "passive"))
    )
    (net (code "180") (name "unconnected-(J3-Pad14)") (class "Default")
      (node (ref "J3") (pin "14") (pinfunction "14_14") (pintype "passive"))
    )
    (net (code "181") (name "unconnected-(J3-Pad15)") (class "Default")
      (node (ref "J3") (pin "15") (pinfunction "15_15") (pintype "passive"))
    )
    (net (code "182") (name "unconnected-(J3-Pad16)") (class "Default")
      (node (ref "J3") (pin "16") (pinfunction "16_16") (pintype "passive"))
    )
    (net (code "183") (name "unconnected-(J3-Pad17)") (class "Default")
      (node (ref "J3") (pin "17") (pinfunction "17_17") (pintype "passive"))
    )
    (net (code "184") (name "unconnected-(J3-Pad18)") (class "Default")
      (node (ref "J3") (pin "18") (pinfunction "18_18") (pintype "passive"))
    )
    (net (code "185") (name "unconnected-(J3-Pad19)") (class "Default")
      (node (ref "J3") (pin "19") (pinfunction "19_19") (pintype "passive"))
    )
    (net (code "186") (name "unconnected-(J3-Pad20)") (class "Default")
      (node (ref "J3") (pin "20") (pinfunction "20_20") (pintype "passive"))
    )
    (net (code "187") (name "unconnected-(J3-Pad21)") (class "Default")
      (node (ref "J3") (pin "21") (pinfunction "21_21") (pintype "passive"))
    )
    (net (code "188") (name "unconnected-(J3-Pad22)") (class "Default")
      (node (ref "J3") (pin "22") (pinfunction "22_22") (pintype "passive"))
    )
    (net (code "189") (name "unconnected-(J3-Pad23)") (class "Default")
      (node (ref "J3") (pin "23") (pinfunction "23_23") (pintype "passive"))
    )
    (net (code "190") (name "unconnected-(J3-Pad24)") (class "Default")
      (node (ref "J3") (pin "24") (pinfunction "24_24") (pintype "passive"))
    )
    (net (code "191") (name "unconnected-(J3-Pad25)") (class "Default")
      (node (ref "J3") (pin "25") (pinfunction "25_25") (pintype "passive"))
    )
    (net (code "192") (name "unconnected-(J3-Pad26)") (class "Default")
      (node (ref "J3") (pin "26") (pinfunction "26_26") (pintype "passive"))
    )
    (net (code "193") (name "unconnected-(J3-Pad27)") (class "Default")
      (node (ref "J3") (pin "27") (pinfunction "27_27") (pintype "passive"))
    )
    (net (code "194") (name "unconnected-(J3-Pad28)") (class "Default")
      (node (ref "J3") (pin "28") (pinfunction "28_28") (pintype "passive"))
    )
    (net (code "195") (name "unconnected-(J3-Pad29)") (class "Default")
      (node (ref "J3") (pin "29") (pinfunction "29_29") (pintype "passive"))
    )
    (net (code "196") (name "unconnected-(J3-Pad30)") (class "Default")
      (node (ref "J3") (pin "30") (pinfunction "30_30") (pintype "passive"))
    )
    (net (code "197") (name "unconnected-(J3-Pad31)") (class "Default")
      (node (ref "J3") (pin "31") (pinfunction "31_31") (pintype "passive"))
    )
    (net (code "198") (name "unconnected-(J3-Pad32)") (class "Default")
      (node (ref "J3") (pin "32") (pinfunction "32_32") (pintype "passive"))
    )
    (net (code "199") (name "unconnected-(J3-Pad33)") (class "Default")
      (node (ref "J3") (pin "33") (pinfunction "33_33") (pintype "passive"))
    )
    (net (code "200") (name "unconnected-(J3-Pad34)") (class "Default")
      (node (ref "J3") (pin "34") (pinfunction "34_34") (pintype "passive"))
    )
    (net (code "201") (name "unconnected-(J3-Pad35)") (class "Default")
      (node (ref "J3") (pin "35") (pinfunction "35_35") (pintype "passive"))
    )
    (net (code "202") (name "unconnected-(J3-Pad36)") (class "Default")
      (node (ref "J3") (pin "36") (pinfunction "36_36") (pintype "passive"))
    )
    (net (code "203") (name "unconnected-(J3-Pad37)") (class "Default")
      (node (ref "J3") (pin "37") (pinfunction "37_37") (pintype "passive"))
    )
    (net (code "204") (name "unconnected-(J3-Pad38)") (class "Default")
      (node (ref "J3") (pin "38") (pinfunction "38_38") (pintype "passive"))
    )
    (net (code "205") (name "unconnected-(J3-Pad39)") (class "Default")
      (node (ref "J3") (pin "39") (pinfunction "39_39") (pintype "passive"))
    )
    (net (code "206") (name "unconnected-(J3-Pad40)") (class "Default")
      (node (ref "J3") (pin "40") (pinfunction "40_40") (pintype "passive"))
    )
    (net (code "207") (name "unconnected-(STM32F407ZET6-3.3V-Pad91)") (class "Default")
      (node (ref "STM32F407ZET6") (pin "91") (pinfunction "3.3V_91") (pintype "passive"))
    )
    (net (code "208") (name "unconnected-(STM32F407ZET6-GND-Pad62)") (class "Default")
      (node (ref "STM32F407ZET6") (pin "62") (pinfunction "GND_62") (pintype "passive"))
    )
    (net (code "209") (name "unconnected-(STM32F407ZET6-GND-Pad92)") (class "Default")
      (node (ref "STM32F407ZET6") (pin "92") (pinfunction "GND_92") (pintype "passive"))
    )
    (net (code "210") (name "unconnected-(STM32F407ZET6-PA8-Pad116)") (class "Default")
      (node (ref "STM32F407ZET6") (pin "116") (pinfunction "PA8_116") (pintype "passive"))
    )
    (net (code "211") (name "unconnected-(STM32F407ZET6-PB2-Pad72)") (class "Default")
      (node (ref "STM32F407ZET6") (pin "72") (pinfunction "PB2_72") (pintype "passive"))
    )
    (net (code "212") (name "unconnected-(STM32F407ZET6-PB10-Pad89)") (class "Default")
      (node (ref "STM32F407ZET6") (pin "89") (pinfunction "PB10_89") (pintype "passive"))
    )
    (net (code "213") (name "unconnected-(STM32F407ZET6-PB11-Pad90)") (class "Default")
      (node (ref "STM32F407ZET6") (pin "90") (pinfunction "PB11_90") (pintype "passive"))
    )
    (net (code "214") (name "unconnected-(STM32F407ZET6-PB14-Pad95)") (class "Default")
      (node (ref "STM32F407ZET6") (pin "95") (pinfunction "PB14_95") (pintype "passive"))
    )
    (net (code "215") (name "unconnected-(STM32F407ZET6-PB15-Pad96)") (class "Default")
      (node (ref "STM32F407ZET6") (pin "96") (pinfunction "PB15_96") (pintype "passive"))
    )
    (net (code "216") (name "unconnected-(STM32F407ZET6-PC10-Pad3)") (class "Default")
      (node (ref "STM32F407ZET6") (pin "3") (pinfunction "PC10_3") (pintype "passive"))
    )
    (net (code "217") (name "unconnected-(STM32F407ZET6-PC11-Pad4)") (class "Default")
      (node (ref "STM32F407ZET6") (pin "4") (pinfunction "PC11_4") (pintype "passive"))
    )
    (net (code "218") (name "unconnected-(STM32F407ZET6-PC12-Pad5)") (class "Default")
      (node (ref "STM32F407ZET6") (pin "5") (pinfunction "PC12_5") (pintype "passive"))
    )
    (net (code "219") (name "unconnected-(STM32F407ZET6-PC13-Pad37)") (class "Default")
      (node (ref "STM32F407ZET6") (pin "37") (pinfunction "PC13_37") (pintype "passive"))
    )
    (net (code "220") (name "unconnected-(STM32F407ZET6-PC14-Pad38)") (class "Default")
      (node (ref "STM32F407ZET6") (pin "38") (pinfunction "PC14_38") (pintype "passive"))
    )
    (net (code "221") (name "unconnected-(STM32F407ZET6-PC15-Pad39)") (class "Default")
      (node (ref "STM32F407ZET6") (pin "39") (pinfunction "PC15_39") (pintype "passive"))
    )
    (net (code "222") (name "unconnected-(STM32F407ZET6-PD2-Pad8)") (class "Default")
      (node (ref "STM32F407ZET6") (pin "8") (pinfunction "PD2_8") (pintype "passive"))
    )
    (net (code "223") (name "unconnected-(STM32F407ZET6-PD3-Pad9)") (class "Default")
      (node (ref "STM32F407ZET6") (pin "9") (pinfunction "PD3_9") (pintype "passive"))
    )
    (net (code "224") (name "unconnected-(STM32F407ZET6-PD4-Pad10)") (class "Default")
      (node (ref "STM32F407ZET6") (pin "10") (pinfunction "PD4_10") (pintype "passive"))
    )
    (net (code "225") (name "unconnected-(STM32F407ZET6-PD7-Pad13)") (class "Default")
      (node (ref "STM32F407ZET6") (pin "13") (pinfunction "PD7_13") (pintype "passive"))
    )
    (net (code "226") (name "unconnected-(STM32F407ZET6-PD10-Pad99)") (class "Default")
      (node (ref "STM32F407ZET6") (pin "99") (pinfunction "PD10_99") (pintype "passive"))
    )
    (net (code "227") (name "unconnected-(STM32F407ZET6-PD11-Pad100)") (class "Default")
      (node (ref "STM32F407ZET6") (pin "100") (pinfunction "PD11_100") (pintype "passive"))
    )
    (net (code "228") (name "unconnected-(STM32F407ZET6-PE7-Pad80)") (class "Default")
      (node (ref "STM32F407ZET6") (pin "80") (pinfunction "PE7_80") (pintype "passive"))
    )
    (net (code "229") (name "unconnected-(STM32F407ZET6-PE8-Pad81)") (class "Default")
      (node (ref "STM32F407ZET6") (pin "81") (pinfunction "PE8_81") (pintype "passive"))
    )
    (net (code "230") (name "unconnected-(STM32F407ZET6-PE10-Pad83)") (class "Default")
      (node (ref "STM32F407ZET6") (pin "83") (pinfunction "PE10_83") (pintype "passive"))
    )
    (net (code "231") (name "unconnected-(STM32F407ZET6-PE12-Pad85)") (class "Default")
      (node (ref "STM32F407ZET6") (pin "85") (pinfunction "PE12_85") (pintype "passive"))
    )
    (net (code "232") (name "unconnected-(STM32F407ZET6-PE15-Pad88)") (class "Default")
      (node (ref "STM32F407ZET6") (pin "88") (pinfunction "PE15_88") (pintype "passive"))
    )
    (net (code "233") (name "unconnected-(STM32F407ZET6-PF0-Pad40)") (class "Default")
      (node (ref "STM32F407ZET6") (pin "40") (pinfunction "PF0_40") (pintype "passive"))
    )
    (net (code "234") (name "unconnected-(STM32F407ZET6-PF1-Pad41)") (class "Default")
      (node (ref "STM32F407ZET6") (pin "41") (pinfunction "PF1_41") (pintype "passive"))
    )
    (net (code "235") (name "unconnected-(STM32F407ZET6-PF2-Pad42)") (class "Default")
      (node (ref "STM32F407ZET6") (pin "42") (pinfunction "PF2_42") (pintype "passive"))
    )
    (net (code "236") (name "unconnected-(STM32F407ZET6-PF9-Pad49)") (class "Default")
      (node (ref "STM32F407ZET6") (pin "49") (pinfunction "PF9_49") (pintype "passive"))
    )
    (net (code "237") (name "unconnected-(STM32F407ZET6-PF10-Pad50)") (class "Default")
      (node (ref "STM32F407ZET6") (pin "50") (pinfunction "PF10_50") (pintype "passive"))
    )
    (net (code "238") (name "unconnected-(STM32F407ZET6-RST-Pad51)") (class "Default")
      (node (ref "STM32F407ZET6") (pin "51") (pinfunction "RST_51") (pintype "passive"))
    )
    (net (code "239") (name "unconnected-(STM32F407ZET6-VBAT-Pad36)") (class "Default")
      (node (ref "STM32F407ZET6") (pin "36") (pinfunction "VBAT_36") (pintype "passive"))
    )
  )
)
